# LcsNodes-Extension-Combo-1-Board-B_02_00.net
KiCad netlist of a schematic drawn in EasyEDA
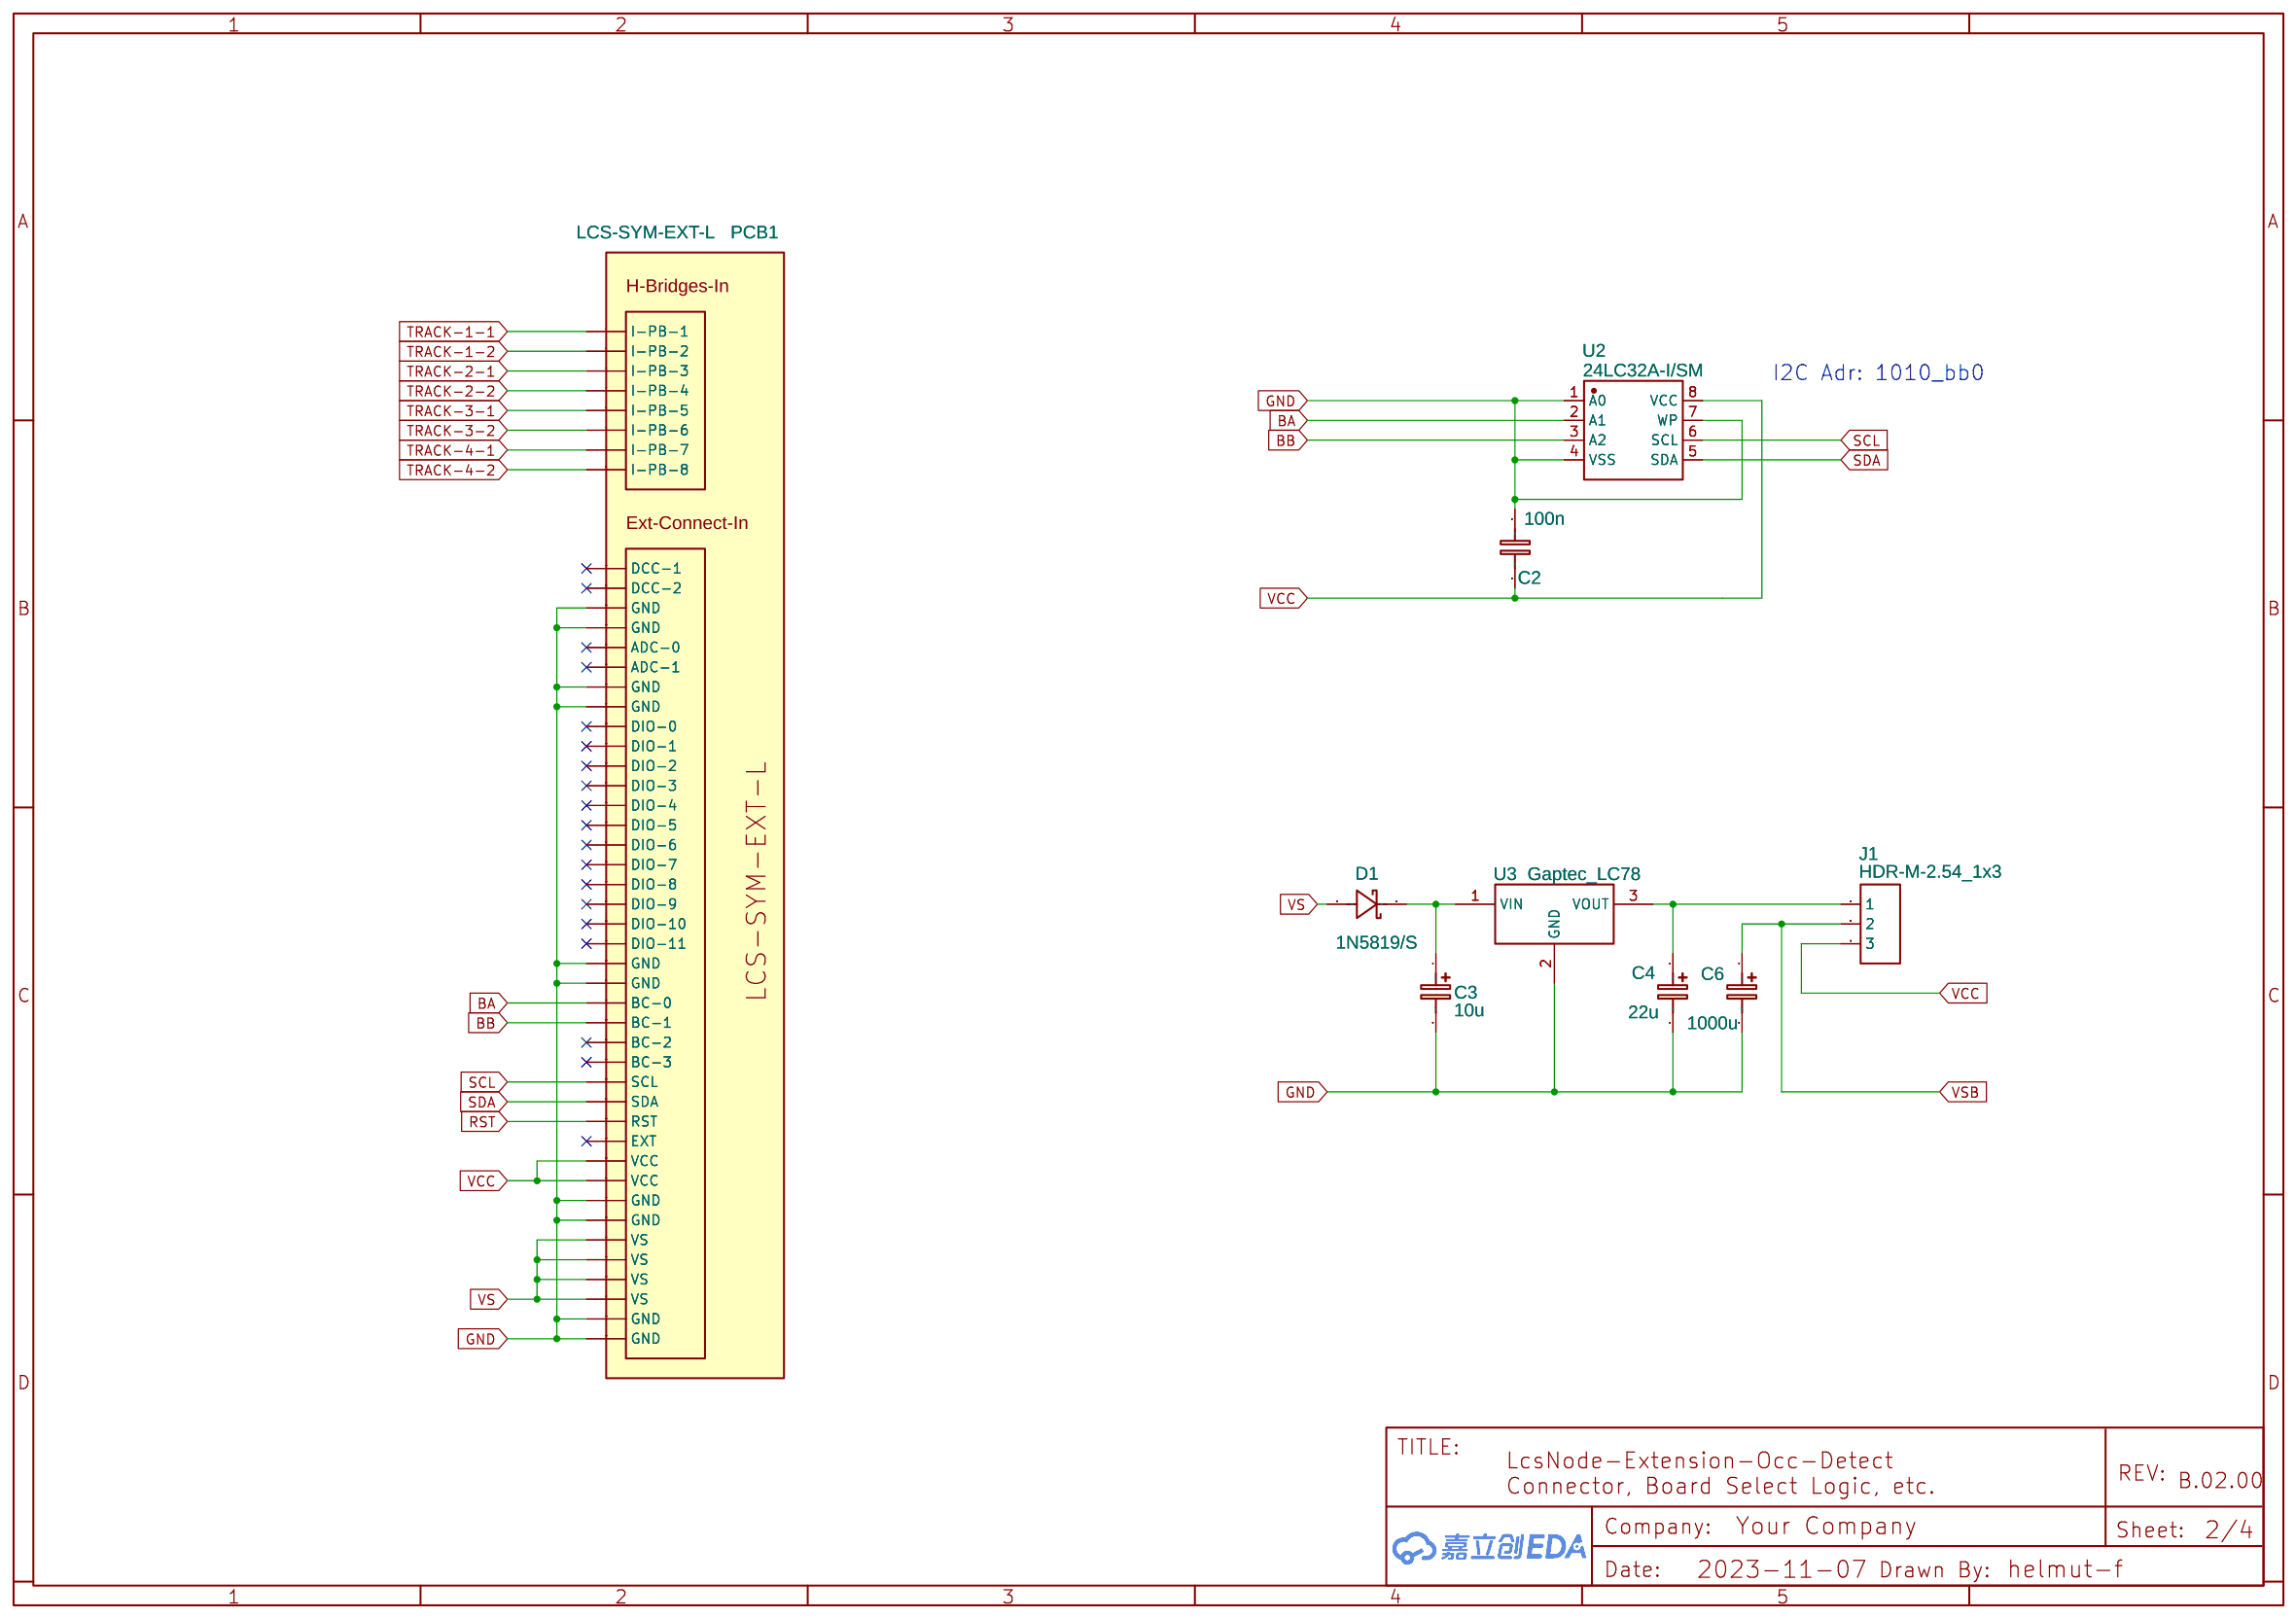
[diagram p0: Connector-and-Logic]
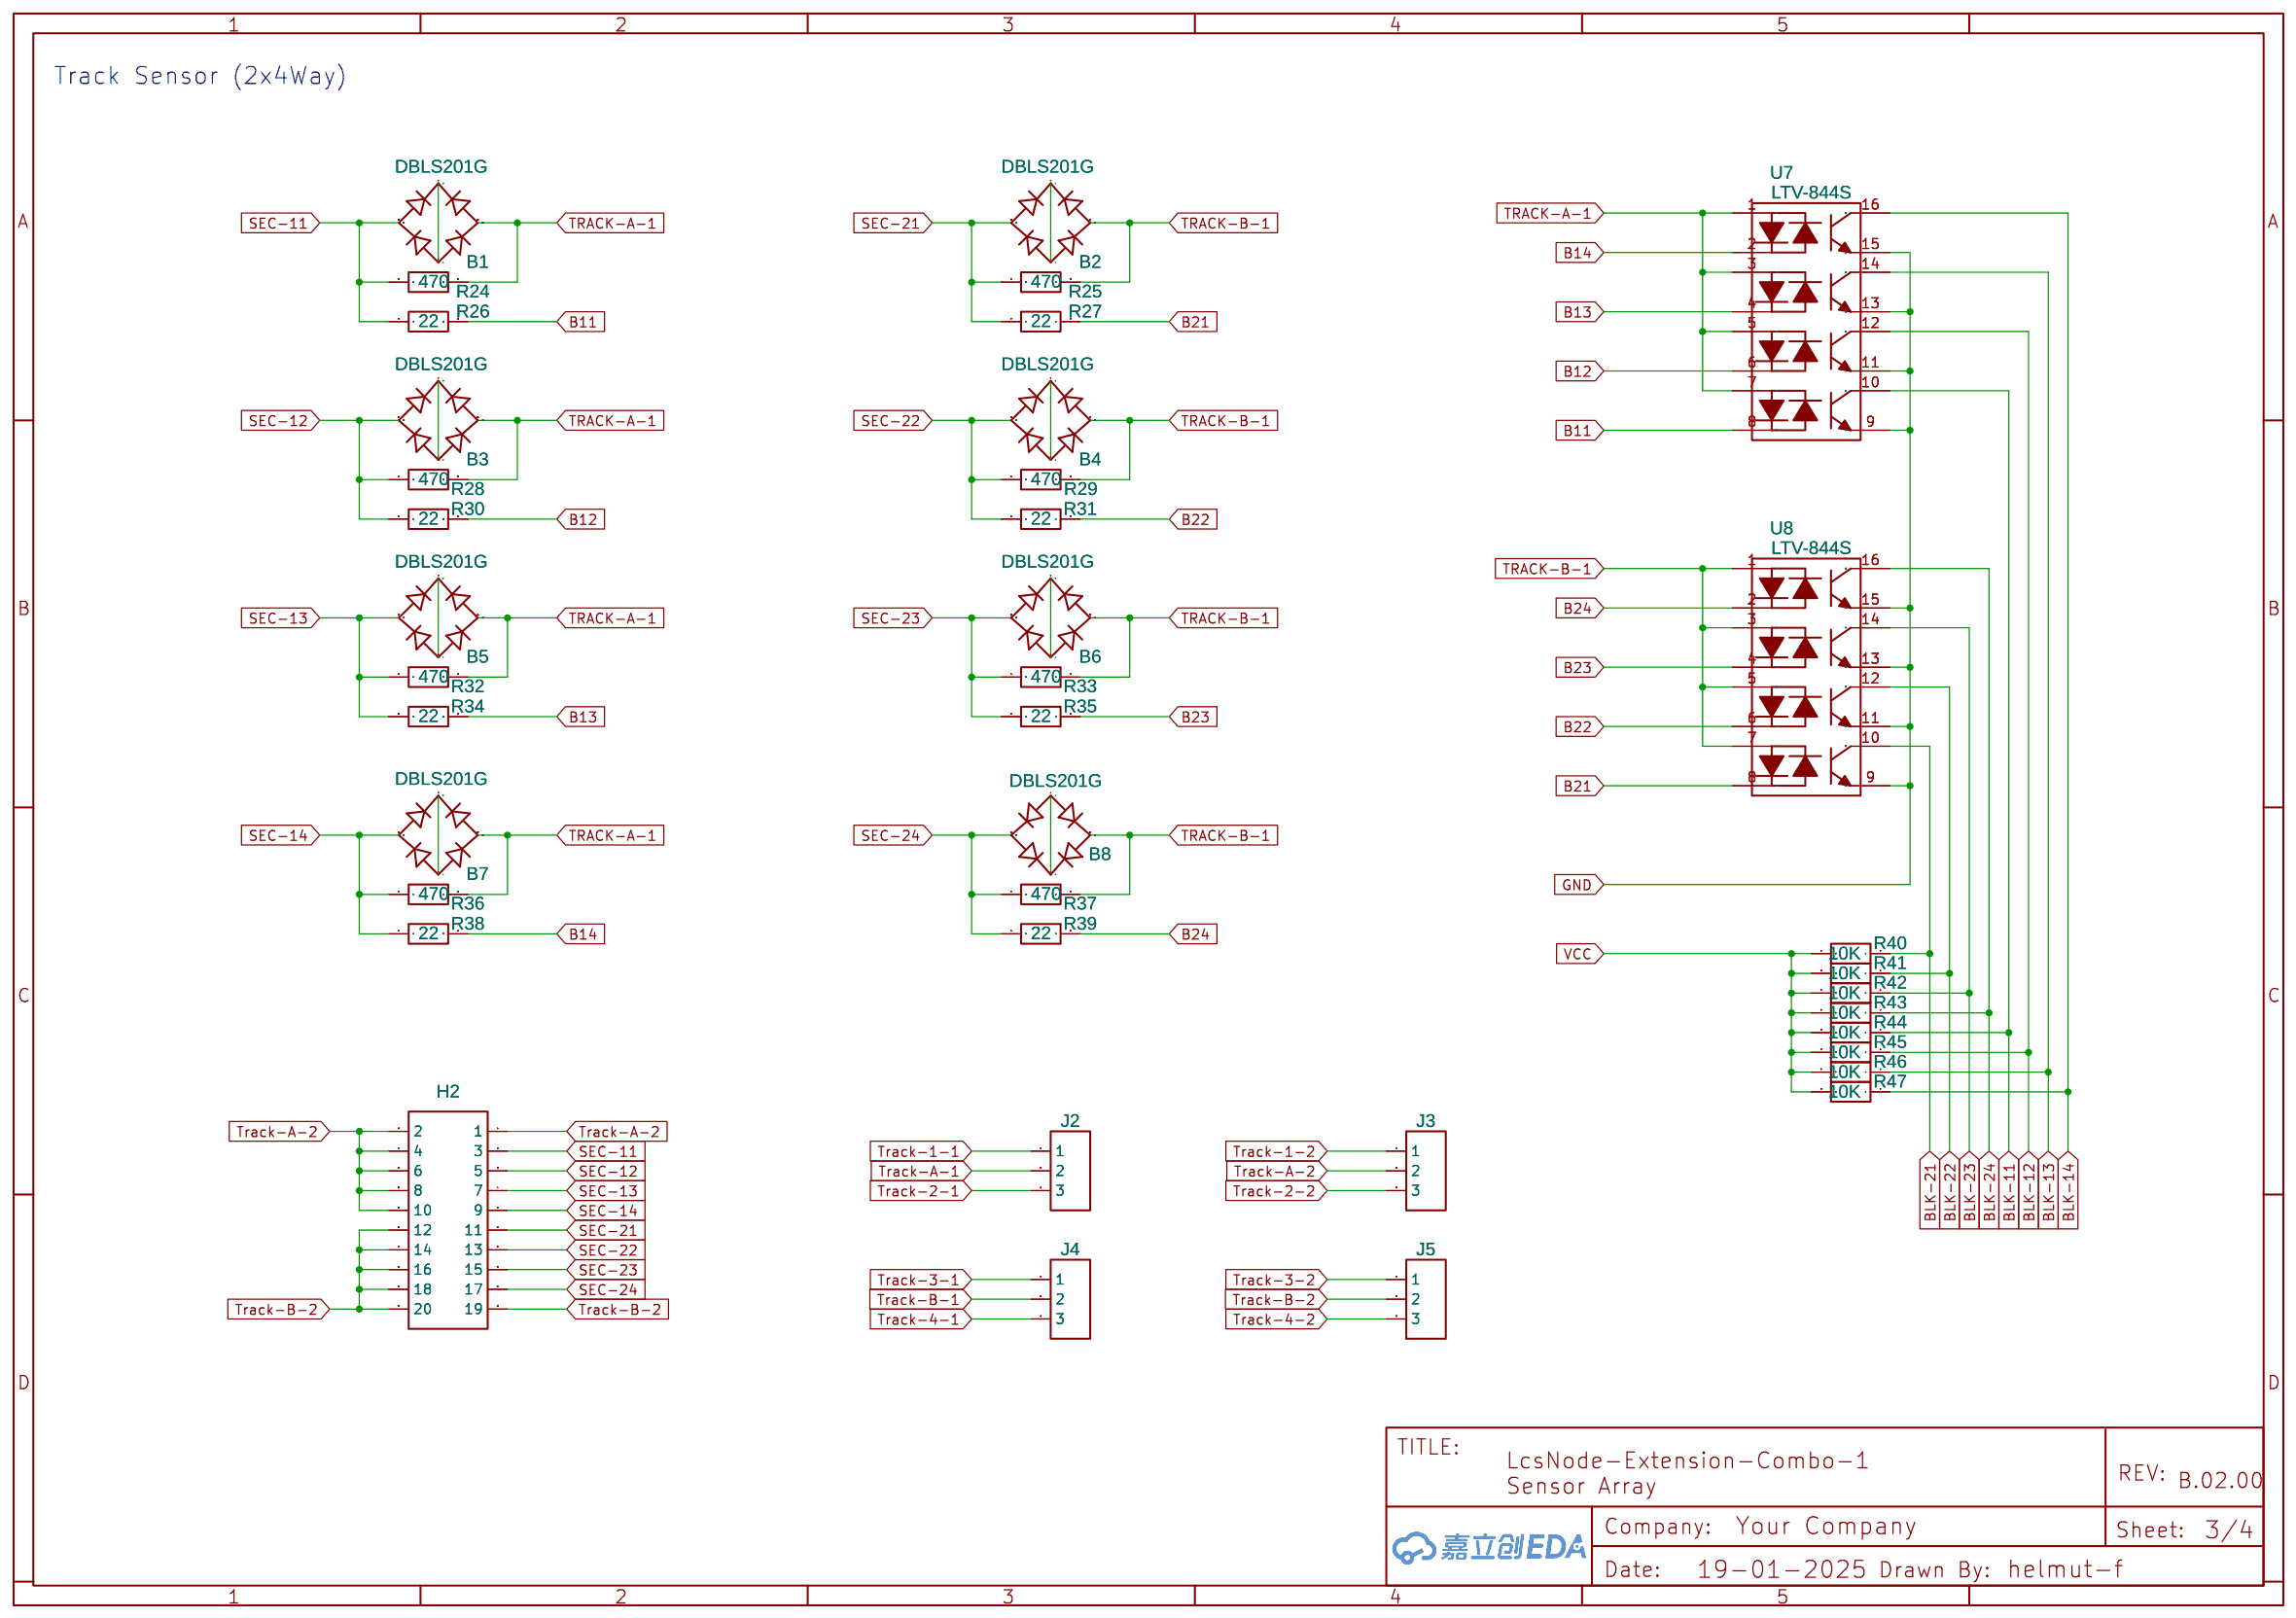
[diagram p1: Sensor-Array]
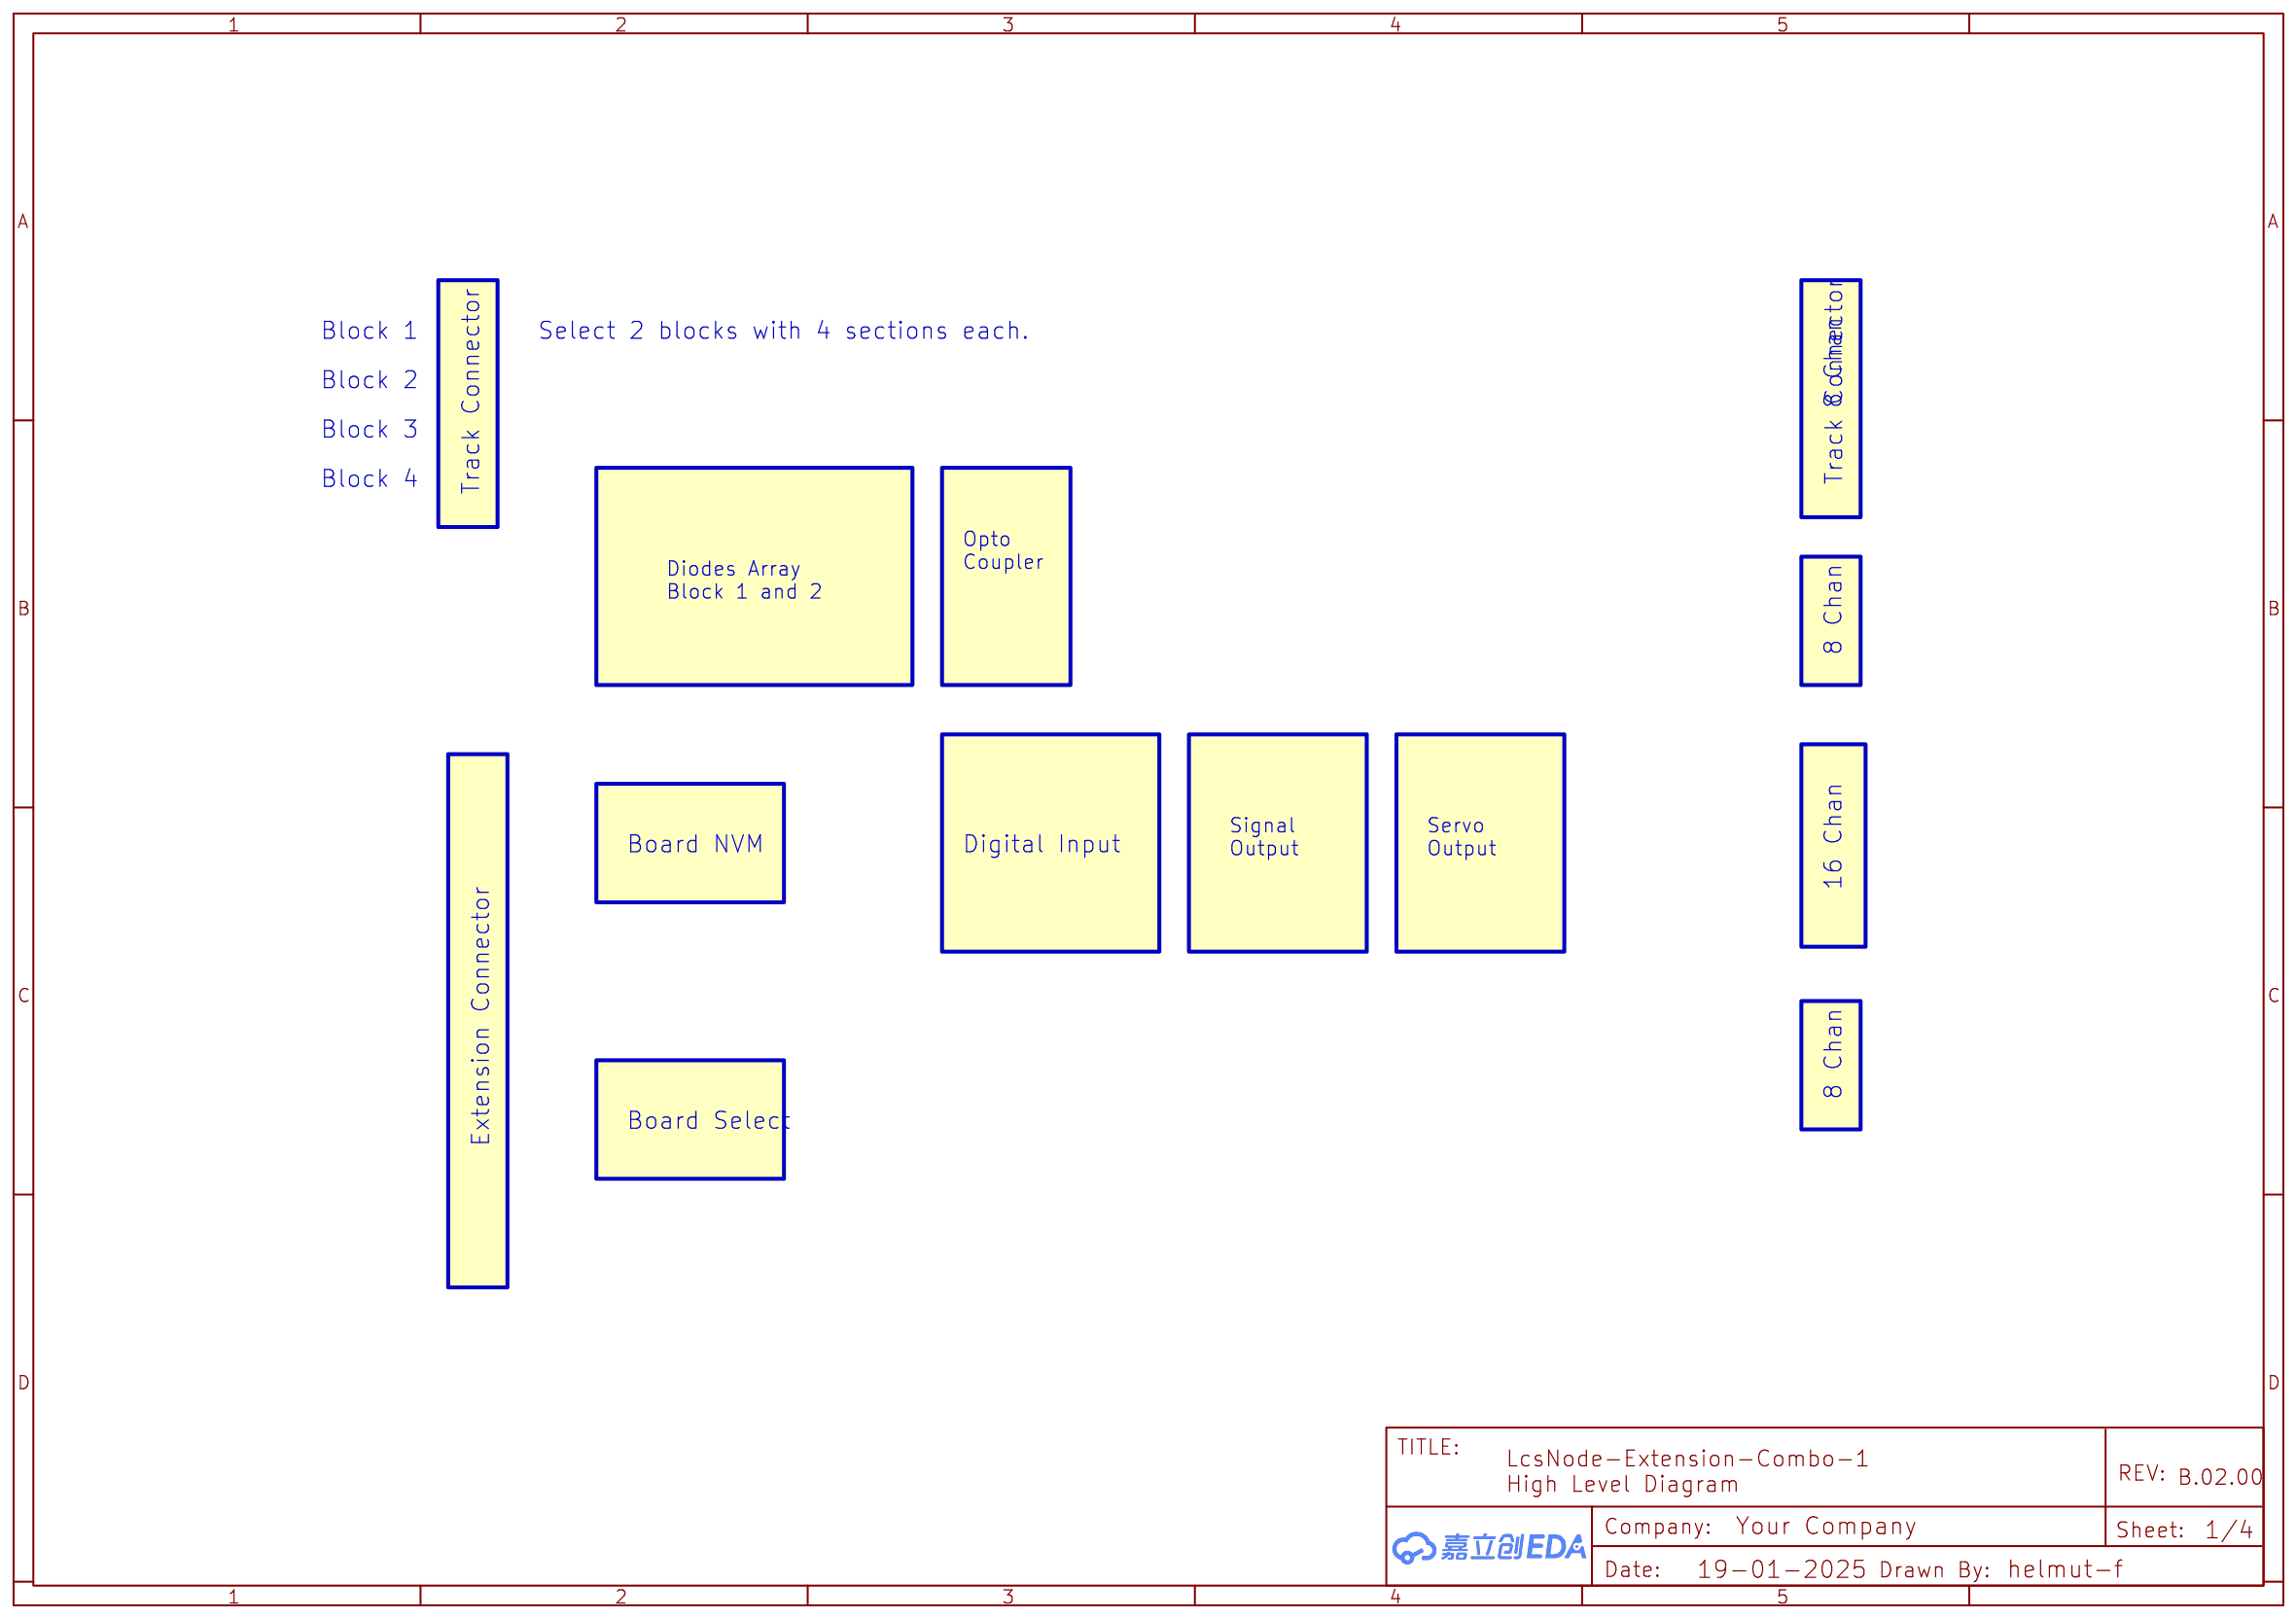
[diagram p2: High Level Schematic]
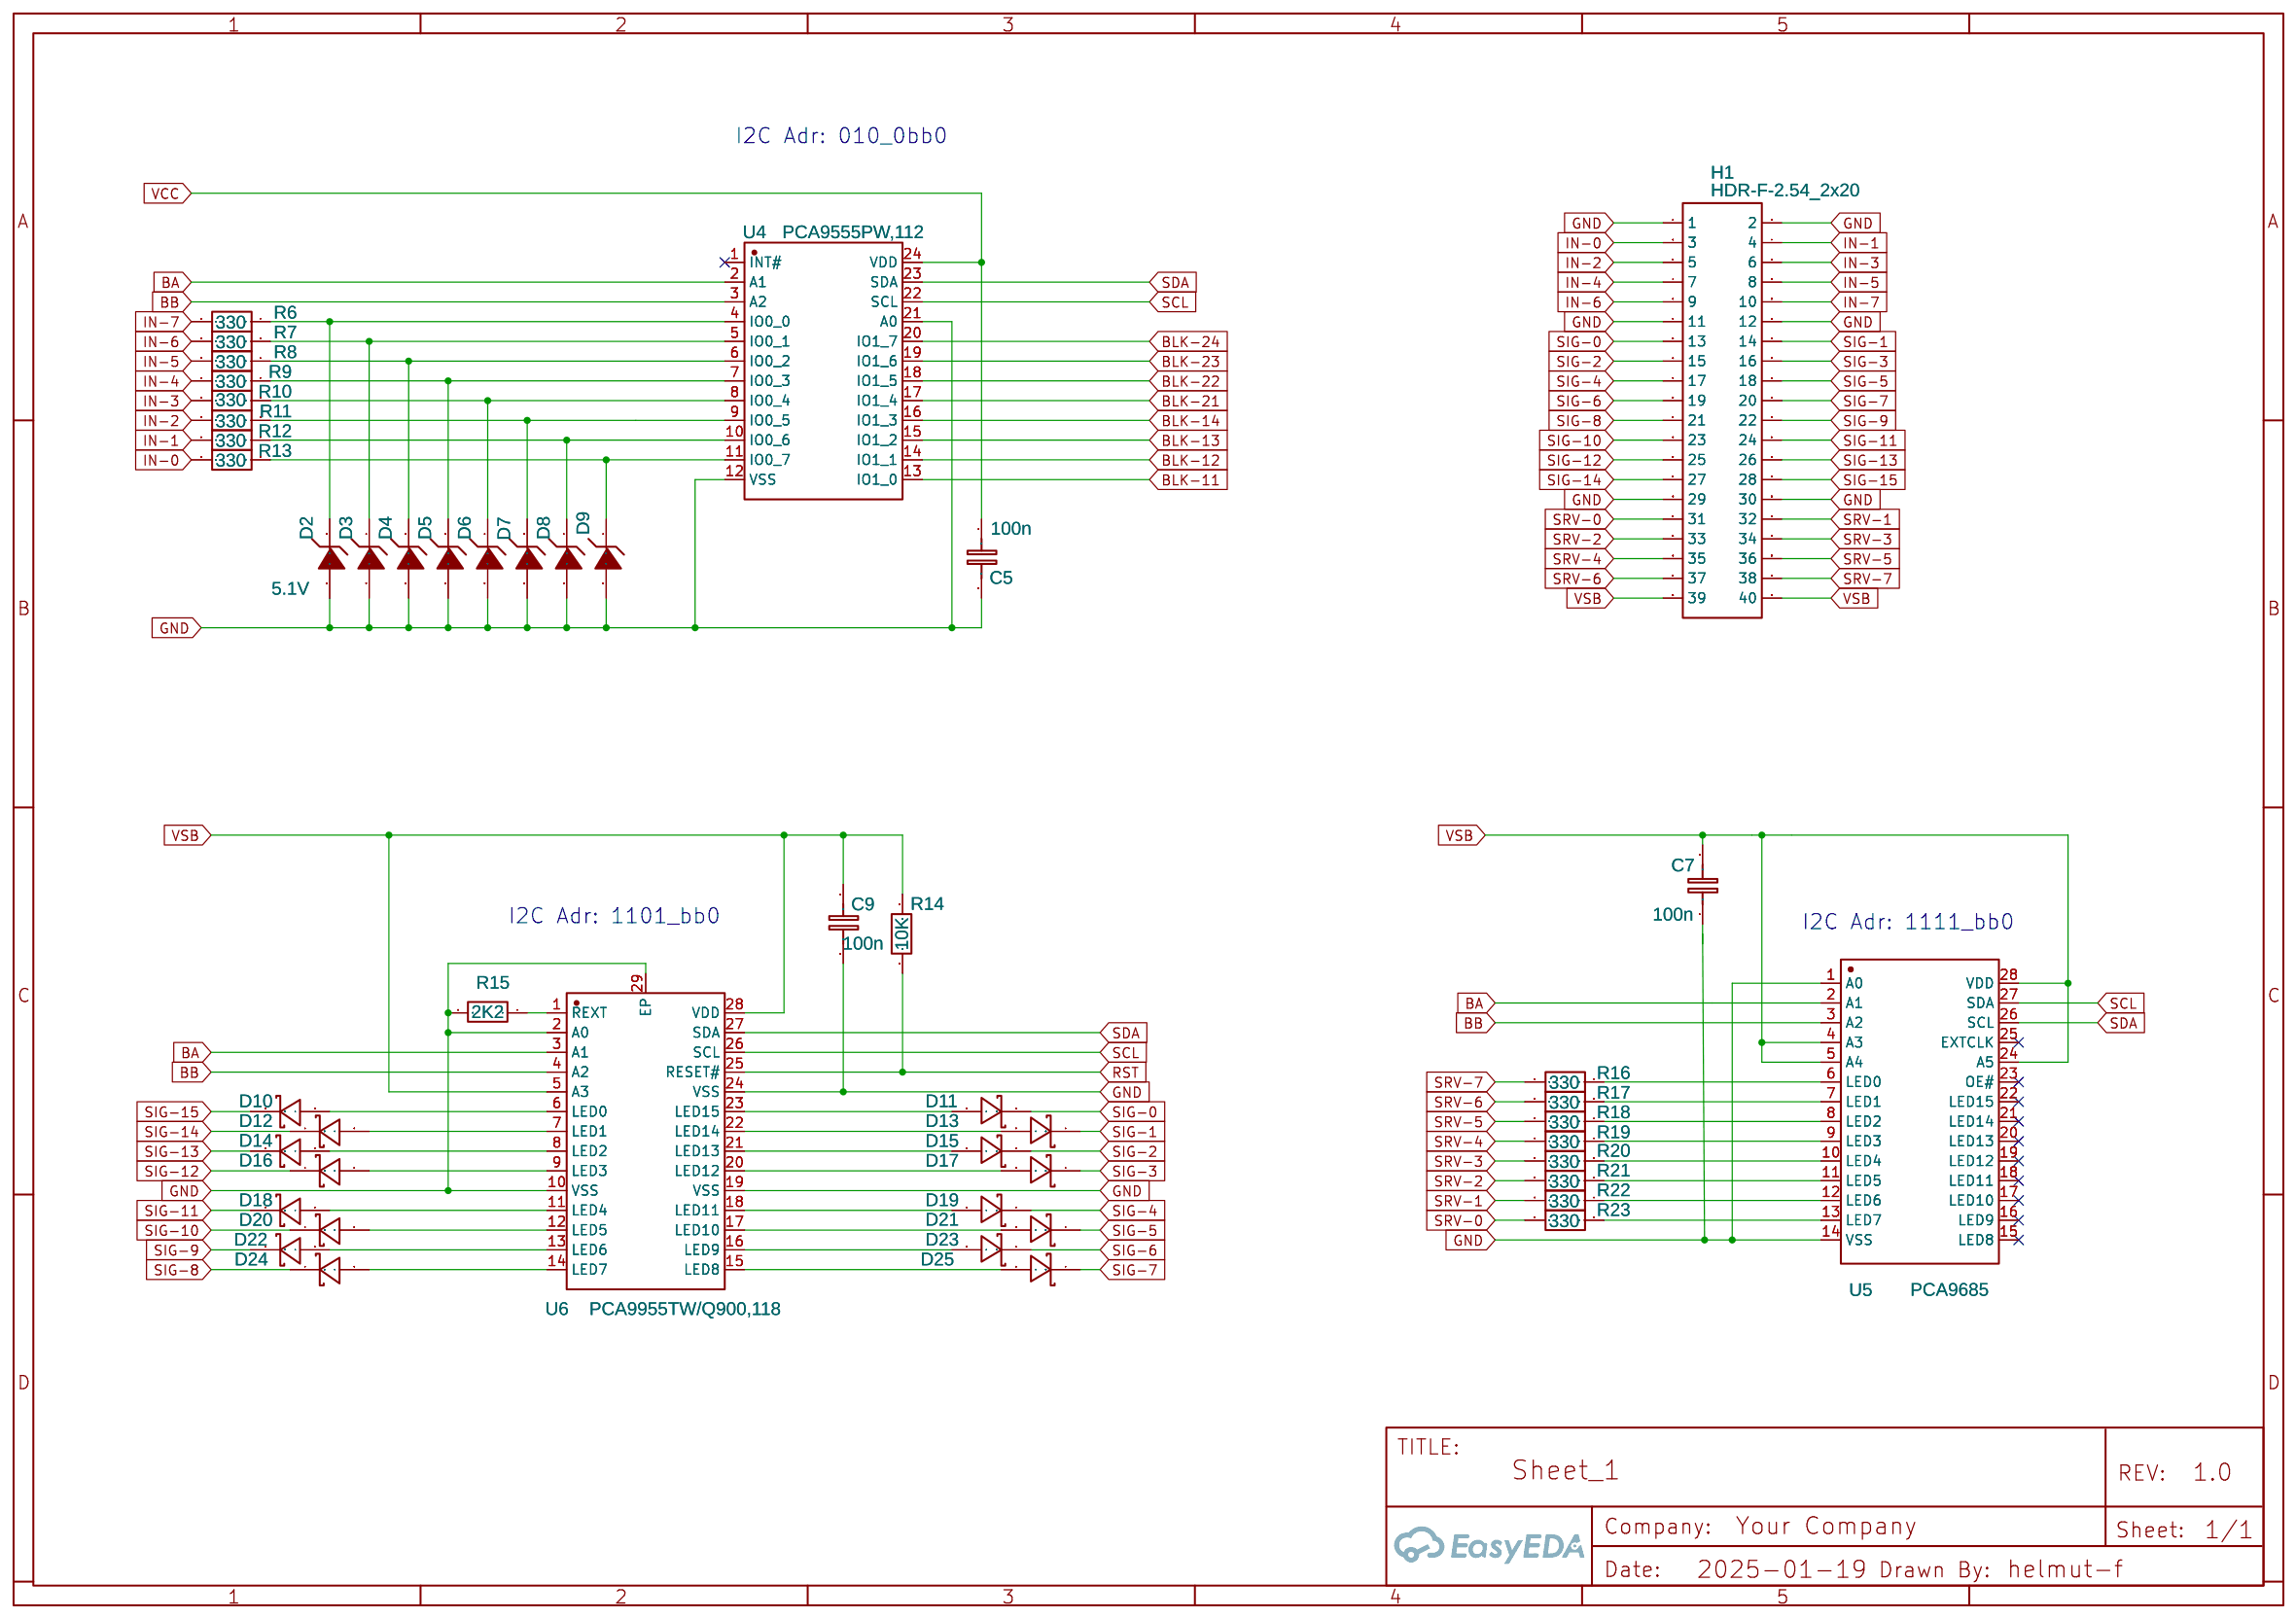
[diagram p3: GPIO, Servo, Signal]

(export (version "E")
  (design (tool "Eeschema 10.0.6"))
  (components
    (comp (ref "C2") (value "100n") (libsource (lib "") (part "C_0603_EU")))
    (comp (ref "C3") (value "10u") (libsource (lib "") (part "CE_SMD_D5.0×H5.5_EU")))
    (comp (ref "C4") (value "22u") (libsource (lib "") (part "CE_SMD_D5.0×H5.5_EU")))
    (comp (ref "C6") (value "1000u") (libsource (lib "") (part "CE_TH_D4.0×F1.5_EU")))
    (comp (ref "D1") (value "1N5819/S") (libsource (lib "") (part "1N5819/S")))
    (comp (ref "J1") (value "HDR-M-2.54_1x3") (libsource (lib "") (part "HDR-M-2.54_1x3")))
    (comp (ref "PCB1") (value "LCS-SYM-EXT-L") (libsource (lib "") (part "LCS-SYM-EXT-L")))
    (comp (ref "U2")
      (value "24LC32A-I/SM")
      (fields (field (name "Manufacturer") "MICROCHIP(美国微芯)"))
      (libsource (lib "") (part "24LC32A-I/SM"))
    )
    (comp (ref "U3") (value "Gaptec_LC78") (libsource (lib "") (part "Gaptec_LC78")))
    (comp (ref "B1") (value "DBLS201G") (libsource (lib "") (part "DBLS201G")))
    (comp (ref "B2") (value "DBLS201G") (libsource (lib "") (part "DBLS201G_2")))
    (comp (ref "B3") (value "DBLS201G") (libsource (lib "") (part "DBLS201G")))
    (comp (ref "B4") (value "DBLS201G") (libsource (lib "") (part "DBLS201G_2")))
    (comp (ref "B5") (value "DBLS201G") (libsource (lib "") (part "DBLS201G")))
    (comp (ref "B6") (value "DBLS201G") (libsource (lib "") (part "DBLS201G_2")))
    (comp (ref "B7") (value "DBLS201G") (libsource (lib "") (part "DBLS201G")))
    (comp (ref "B8") (value "DBLS201G") (libsource (lib "") (part "DBLS201G_1")))
    (comp (ref "H2") (value "HDR-F-2.54_2x10") (libsource (lib "") (part "HDR-F-2.54_2x10")))
    (comp (ref "J2") (value "HDR-M-2.54_1x3") (libsource (lib "") (part "HDR-M-2.54_1x3")))
    (comp (ref "J3") (value "HDR-M-2.54_1x3") (libsource (lib "") (part "HDR-M-2.54_1x3")))
    (comp (ref "J4") (value "HDR-M-2.54_1x3") (libsource (lib "") (part "HDR-M-2.54_1x3")))
    (comp (ref "J5") (value "HDR-M-2.54_1x3") (libsource (lib "") (part "HDR-M-2.54_1x3")))
    (comp (ref "R24") (value "470") (libsource (lib "") (part "R_AXIAL-0.3_EU_1")))
    (comp (ref "R25") (value "470") (libsource (lib "") (part "R_AXIAL-0.3_EU_1")))
    (comp (ref "R26") (value "22") (libsource (lib "") (part "R_AXIAL-0.3_EU_1")))
    (comp (ref "R27") (value "22") (libsource (lib "") (part "R_AXIAL-0.3_EU_1")))
    (comp (ref "R28") (value "470") (libsource (lib "") (part "R_AXIAL-0.3_EU_1")))
    (comp (ref "R29") (value "470") (libsource (lib "") (part "R_AXIAL-0.3_EU_1")))
    (comp (ref "R30") (value "22") (libsource (lib "") (part "R_AXIAL-0.3_EU_1")))
    (comp (ref "R31") (value "22") (libsource (lib "") (part "R_AXIAL-0.3_EU_1")))
    (comp (ref "R32") (value "470") (libsource (lib "") (part "R_AXIAL-0.3_EU_1")))
    (comp (ref "R33") (value "470") (libsource (lib "") (part "R_AXIAL-0.3_EU_1")))
    (comp (ref "R34") (value "22") (libsource (lib "") (part "R_AXIAL-0.3_EU_1")))
    (comp (ref "R35") (value "22") (libsource (lib "") (part "R_AXIAL-0.3_EU_1")))
    (comp (ref "R36") (value "470") (libsource (lib "") (part "R_AXIAL-0.3_EU_1")))
    (comp (ref "R37") (value "470") (libsource (lib "") (part "R_AXIAL-0.3_EU_1")))
    (comp (ref "R38") (value "22") (libsource (lib "") (part "R_AXIAL-0.3_EU_1")))
    (comp (ref "R39") (value "22") (libsource (lib "") (part "R_AXIAL-0.3_EU_1")))
    (comp (ref "R40") (value "10K") (libsource (lib "") (part "R_AXIAL-0.3_EU")))
    (comp (ref "R41") (value "10K") (libsource (lib "") (part "R_AXIAL-0.3_EU")))
    (comp (ref "R42") (value "10K") (libsource (lib "") (part "R_AXIAL-0.3_EU")))
    (comp (ref "R43") (value "10K") (libsource (lib "") (part "R_AXIAL-0.3_EU")))
    (comp (ref "R44") (value "10K") (libsource (lib "") (part "R_AXIAL-0.3_EU")))
    (comp (ref "R45") (value "10K") (libsource (lib "") (part "R_AXIAL-0.3_EU")))
    (comp (ref "R46") (value "10K") (libsource (lib "") (part "R_AXIAL-0.3_EU")))
    (comp (ref "R47") (value "10K") (libsource (lib "") (part "R_AXIAL-0.3_EU")))
    (comp (ref "U7")
      (value "LTV-844S")
      (fields (field (name "Manufacturer") "LITEON(台湾光宝)"))
      (libsource (lib "") (part "LTV-844S"))
    )
    (comp (ref "U8")
      (value "LTV-844S")
      (fields (field (name "Manufacturer") "LITEON(台湾光宝)"))
      (libsource (lib "") (part "LTV-844S"))
    )
    (comp (ref "C5") (value "100n") (libsource (lib "") (part "C_0603_EU")))
    (comp (ref "C7") (value "100n") (libsource (lib "") (part "C_0603_EU_2")))
    (comp (ref "C9") (value "100n") (libsource (lib "") (part "C_0603_EU_1")))
    (comp (ref "D2")
      (value "5.1V")
      (fields (field (name "Manufacturer Part") "Diode Zener") (field (name "Manufacturer") "SEMTECH"))
      (libsource (lib "") (part "Diode Zener"))
    )
    (comp (ref "D3")
      (value "5.1V")
      (fields (field (name "Manufacturer Part") "Diode Zener") (field (name "Manufacturer") "SEMTECH"))
      (libsource (lib "") (part "Diode Zener"))
    )
    (comp (ref "D4")
      (value "5.1V")
      (fields (field (name "Manufacturer Part") "Diode Zener") (field (name "Manufacturer") "SEMTECH"))
      (libsource (lib "") (part "Diode Zener"))
    )
    (comp (ref "D5")
      (value "5.1V")
      (fields (field (name "Manufacturer Part") "Diode Zener") (field (name "Manufacturer") "SEMTECH"))
      (libsource (lib "") (part "Diode Zener"))
    )
    (comp (ref "D6")
      (value "5.1V")
      (fields (field (name "Manufacturer Part") "Diode Zener") (field (name "Manufacturer") "SEMTECH"))
      (libsource (lib "") (part "Diode Zener"))
    )
    (comp (ref "D7")
      (value "5.1V")
      (fields (field (name "Manufacturer Part") "Diode Zener") (field (name "Manufacturer") "SEMTECH"))
      (libsource (lib "") (part "Diode Zener"))
    )
    (comp (ref "D8")
      (value "5.1V")
      (fields (field (name "Manufacturer Part") "Diode Zener") (field (name "Manufacturer") "SEMTECH"))
      (libsource (lib "") (part "Diode Zener"))
    )
    (comp (ref "D9")
      (value "5.1V")
      (fields (field (name "Manufacturer Part") "Diode Zener") (field (name "Manufacturer") "SEMTECH"))
      (libsource (lib "") (part "Diode Zener"))
    )
    (comp (ref "D10")
      (value "BAS85")
      (fields (field (name "Manufacturer") "SHIKUES(时科)"))
      (libsource (lib "") (part "BAS85"))
    )
    (comp (ref "D11")
      (value "BAS85")
      (fields (field (name "Manufacturer") "SHIKUES(时科)"))
      (libsource (lib "") (part "BAS85_1"))
    )
    (comp (ref "D12")
      (value "BAS85")
      (fields (field (name "Manufacturer") "SHIKUES(时科)"))
      (libsource (lib "") (part "BAS85"))
    )
    (comp (ref "D13")
      (value "BAS85")
      (fields (field (name "Manufacturer") "SHIKUES(时科)"))
      (libsource (lib "") (part "BAS85_1"))
    )
    (comp (ref "D14")
      (value "BAS85")
      (fields (field (name "Manufacturer") "SHIKUES(时科)"))
      (libsource (lib "") (part "BAS85"))
    )
    (comp (ref "D15")
      (value "BAS85")
      (fields (field (name "Manufacturer") "SHIKUES(时科)"))
      (libsource (lib "") (part "BAS85_1"))
    )
    (comp (ref "D16")
      (value "BAS85")
      (fields (field (name "Manufacturer") "SHIKUES(时科)"))
      (libsource (lib "") (part "BAS85"))
    )
    (comp (ref "D17")
      (value "BAS85")
      (fields (field (name "Manufacturer") "SHIKUES(时科)"))
      (libsource (lib "") (part "BAS85_1"))
    )
    (comp (ref "D18")
      (value "BAS85")
      (fields (field (name "Manufacturer") "SHIKUES(时科)"))
      (libsource (lib "") (part "BAS85"))
    )
    (comp (ref "D19")
      (value "BAS85")
      (fields (field (name "Manufacturer") "SHIKUES(时科)"))
      (libsource (lib "") (part "BAS85_1"))
    )
    (comp (ref "D20")
      (value "BAS85")
      (fields (field (name "Manufacturer") "SHIKUES(时科)"))
      (libsource (lib "") (part "BAS85"))
    )
    (comp (ref "D21")
      (value "BAS85")
      (fields (field (name "Manufacturer") "SHIKUES(时科)"))
      (libsource (lib "") (part "BAS85_1"))
    )
    (comp (ref "D22")
      (value "BAS85")
      (fields (field (name "Manufacturer") "SHIKUES(时科)"))
      (libsource (lib "") (part "BAS85"))
    )
    (comp (ref "D23")
      (value "BAS85")
      (fields (field (name "Manufacturer") "SHIKUES(时科)"))
      (libsource (lib "") (part "BAS85_1"))
    )
    (comp (ref "D24")
      (value "BAS85")
      (fields (field (name "Manufacturer") "SHIKUES(时科)"))
      (libsource (lib "") (part "BAS85"))
    )
    (comp (ref "D25")
      (value "BAS85")
      (fields (field (name "Manufacturer") "SHIKUES(时科)"))
      (libsource (lib "") (part "BAS85_1"))
    )
    (comp (ref "H1") (value "HDR-F-2.54_2x20") (libsource (lib "") (part "HDR-F-2.54_2x20")))
    (comp (ref "R6") (value "330") (libsource (lib "") (part "R_AXIAL-0.3_EU")))
    (comp (ref "R7") (value "330") (libsource (lib "") (part "R_AXIAL-0.3_EU")))
    (comp (ref "R8") (value "330") (libsource (lib "") (part "R_AXIAL-0.3_EU")))
    (comp (ref "R9") (value "330") (libsource (lib "") (part "R_AXIAL-0.3_EU")))
    (comp (ref "R10") (value "330") (libsource (lib "") (part "R_AXIAL-0.3_EU")))
    (comp (ref "R11") (value "330") (libsource (lib "") (part "R_AXIAL-0.3_EU")))
    (comp (ref "R12") (value "330") (libsource (lib "") (part "R_AXIAL-0.3_EU")))
    (comp (ref "R13") (value "330") (libsource (lib "") (part "R_AXIAL-0.3_EU")))
    (comp (ref "R14") (value "10K") (libsource (lib "") (part "R_AXIAL-0.3_EU_1")))
    (comp (ref "R15") (value "2K2") (libsource (lib "") (part "R_AXIAL-0.3_EU_2")))
    (comp (ref "R16") (value "330") (libsource (lib "") (part "R_AXIAL-0.3_EU")))
    (comp (ref "R17") (value "330") (libsource (lib "") (part "R_AXIAL-0.3_EU")))
    (comp (ref "R18") (value "330") (libsource (lib "") (part "R_AXIAL-0.3_EU")))
    (comp (ref "R19") (value "330") (libsource (lib "") (part "R_AXIAL-0.3_EU")))
    (comp (ref "R20") (value "330") (libsource (lib "") (part "R_AXIAL-0.3_EU")))
    (comp (ref "R21") (value "330") (libsource (lib "") (part "R_AXIAL-0.3_EU")))
    (comp (ref "R22") (value "330") (libsource (lib "") (part "R_AXIAL-0.3_EU")))
    (comp (ref "R23") (value "330") (libsource (lib "") (part "R_AXIAL-0.3_EU")))
    (comp (ref "U4")
      (value "PCA9555PW,112")
      (fields (field (name "Manufacturer") "NXP(恩智浦)"))
      (libsource (lib "") (part "PCA9555PW,112"))
    )
    (comp (ref "U5")
      (value "PCA9685")
      (fields (field (name "Manufacturer Part") "PCA9685PW/Q900,118") (field (name "Manufacturer") "NXP"))
      (libsource (lib "") (part "PCA9685PW/Q900,118"))
    )
    (comp (ref "U6")
      (value "PCA9955TW/Q900,118")
      (fields (field (name "Manufacturer") "NXP(恩智浦)"))
      (libsource (lib "") (part "PCA9955TW/Q900,118"))
    )
  )
  (nets
    (net (code "1") (name "B11") (class "Default")
      (node (ref "R26") (pin "2") (pinfunction "2_2") (pintype "unspecified"))
      (node (ref "U7") (pin "8") (pinfunction "8_8") (pintype "unspecified"))
    )
    (net (code "2") (name "B12") (class "Default")
      (node (ref "R30") (pin "2") (pinfunction "2_2") (pintype "unspecified"))
      (node (ref "U7") (pin "6") (pinfunction "6_6") (pintype "unspecified"))
    )
    (net (code "3") (name "B13") (class "Default")
      (node (ref "R34") (pin "2") (pinfunction "2_2") (pintype "unspecified"))
      (node (ref "U7") (pin "4") (pinfunction "4_4") (pintype "unspecified"))
    )
    (net (code "4") (name "B14") (class "Default")
      (node (ref "R38") (pin "2") (pinfunction "2_2") (pintype "unspecified"))
      (node (ref "U7") (pin "2") (pinfunction "2_2") (pintype "unspecified"))
    )
    (net (code "5") (name "B21") (class "Default")
      (node (ref "R27") (pin "2") (pinfunction "2_2") (pintype "unspecified"))
      (node (ref "U8") (pin "8") (pinfunction "8_8") (pintype "unspecified"))
    )
    (net (code "6") (name "B22") (class "Default")
      (node (ref "R31") (pin "2") (pinfunction "2_2") (pintype "unspecified"))
      (node (ref "U8") (pin "6") (pinfunction "6_6") (pintype "unspecified"))
    )
    (net (code "7") (name "B23") (class "Default")
      (node (ref "R35") (pin "2") (pinfunction "2_2") (pintype "unspecified"))
      (node (ref "U8") (pin "4") (pinfunction "4_4") (pintype "unspecified"))
    )
    (net (code "8") (name "B24") (class "Default")
      (node (ref "R39") (pin "2") (pinfunction "2_2") (pintype "unspecified"))
      (node (ref "U8") (pin "2") (pinfunction "2_2") (pintype "unspecified"))
    )
    (net (code "9") (name "BA") (class "Default")
      (node (ref "PCB1") (pin "32") (pinfunction "BC-0_32") (pintype "unspecified"))
      (node (ref "U2") (pin "2") (pinfunction "A1_2") (pintype "unspecified"))
      (node (ref "U4") (pin "2") (pinfunction "A1_2") (pintype "unspecified"))
      (node (ref "U5") (pin "2") (pinfunction "A1_2") (pintype "unspecified"))
      (node (ref "U6") (pin "3") (pinfunction "A1_3") (pintype "unspecified"))
    )
    (net (code "10") (name "BB") (class "Default")
      (node (ref "PCB1") (pin "33") (pinfunction "BC-1_33") (pintype "unspecified"))
      (node (ref "U2") (pin "3") (pinfunction "A2_3") (pintype "unspecified"))
      (node (ref "U4") (pin "3") (pinfunction "A2_3") (pintype "unspecified"))
      (node (ref "U5") (pin "3") (pinfunction "A2_3") (pintype "unspecified"))
      (node (ref "U6") (pin "4") (pinfunction "A2_4") (pintype "unspecified"))
    )
    (net (code "11") (name "BLK-11") (class "Default")
      (node (ref "R44") (pin "1") (pinfunction "1_1") (pintype "unspecified"))
      (node (ref "U4") (pin "13") (pinfunction "IO1_0_13") (pintype "unspecified"))
      (node (ref "U7") (pin "10") (pinfunction "10_10") (pintype "unspecified"))
    )
    (net (code "12") (name "BLK-12") (class "Default")
      (node (ref "R45") (pin "1") (pinfunction "1_1") (pintype "unspecified"))
      (node (ref "U4") (pin "14") (pinfunction "IO1_1_14") (pintype "unspecified"))
      (node (ref "U7") (pin "12") (pinfunction "12_12") (pintype "unspecified"))
    )
    (net (code "13") (name "BLK-13") (class "Default")
      (node (ref "R46") (pin "1") (pinfunction "1_1") (pintype "unspecified"))
      (node (ref "U4") (pin "15") (pinfunction "IO1_2_15") (pintype "unspecified"))
      (node (ref "U7") (pin "14") (pinfunction "14_14") (pintype "unspecified"))
    )
    (net (code "14") (name "BLK-14") (class "Default")
      (node (ref "R47") (pin "1") (pinfunction "1_1") (pintype "unspecified"))
      (node (ref "U4") (pin "16") (pinfunction "IO1_3_16") (pintype "unspecified"))
      (node (ref "U7") (pin "16") (pinfunction "16_16") (pintype "unspecified"))
    )
    (net (code "15") (name "BLK-21") (class "Default")
      (node (ref "R40") (pin "1") (pinfunction "1_1") (pintype "unspecified"))
      (node (ref "U4") (pin "17") (pinfunction "IO1_4_17") (pintype "unspecified"))
      (node (ref "U8") (pin "10") (pinfunction "10_10") (pintype "unspecified"))
    )
    (net (code "16") (name "BLK-22") (class "Default")
      (node (ref "R41") (pin "1") (pinfunction "1_1") (pintype "unspecified"))
      (node (ref "U4") (pin "18") (pinfunction "IO1_5_18") (pintype "unspecified"))
      (node (ref "U8") (pin "12") (pinfunction "12_12") (pintype "unspecified"))
    )
    (net (code "17") (name "BLK-23") (class "Default")
      (node (ref "R42") (pin "1") (pinfunction "1_1") (pintype "unspecified"))
      (node (ref "U4") (pin "19") (pinfunction "IO1_6_19") (pintype "unspecified"))
      (node (ref "U8") (pin "14") (pinfunction "14_14") (pintype "unspecified"))
    )
    (net (code "18") (name "BLK-24") (class "Default")
      (node (ref "R43") (pin "1") (pinfunction "1_1") (pintype "unspecified"))
      (node (ref "U4") (pin "20") (pinfunction "IO1_7_20") (pintype "unspecified"))
      (node (ref "U8") (pin "16") (pinfunction "16_16") (pintype "unspecified"))
    )
    (net (code "19") (name "GND") (class "Default")
      (node (ref "C2") (pin "1") (pinfunction "1_1") (pintype "unspecified"))
      (node (ref "C3") (pin "2") (pinfunction "2_2") (pintype "unspecified"))
      (node (ref "C4") (pin "2") (pinfunction "2_2") (pintype "unspecified"))
      (node (ref "C5") (pin "2") (pinfunction "2_2") (pintype "unspecified"))
      (node (ref "C6") (pin "2") (pinfunction "2_2") (pintype "unspecified"))
      (node (ref "C7") (pin "1") (pinfunction "1_1") (pintype "unspecified"))
      (node (ref "C9") (pin "2") (pinfunction "2_2") (pintype "unspecified"))
      (node (ref "D2") (pin "2") (pinfunction "A_2") (pintype "unspecified"))
      (node (ref "D3") (pin "2") (pinfunction "A_2") (pintype "unspecified"))
      (node (ref "D4") (pin "2") (pinfunction "A_2") (pintype "unspecified"))
      (node (ref "D5") (pin "2") (pinfunction "A_2") (pintype "unspecified"))
      (node (ref "D6") (pin "2") (pinfunction "A_2") (pintype "unspecified"))
      (node (ref "D7") (pin "2") (pinfunction "A_2") (pintype "unspecified"))
      (node (ref "D8") (pin "2") (pinfunction "A_2") (pintype "unspecified"))
      (node (ref "D9") (pin "2") (pinfunction "A_2") (pintype "unspecified"))
      (node (ref "H1") (pin "1") (pinfunction "1_1") (pintype "input"))
      (node (ref "H1") (pin "11") (pinfunction "11_11") (pintype "input"))
      (node (ref "H1") (pin "12") (pinfunction "12_12") (pintype "input"))
      (node (ref "H1") (pin "2") (pinfunction "2_2") (pintype "input"))
      (node (ref "H1") (pin "29") (pinfunction "29_29") (pintype "input"))
      (node (ref "H1") (pin "30") (pinfunction "30_30") (pintype "input"))
      (node (ref "PCB1") (pin "12") (pinfunction "GND_12") (pintype "unspecified"))
      (node (ref "PCB1") (pin "13") (pinfunction "GND_13") (pintype "unspecified"))
      (node (ref "PCB1") (pin "16") (pinfunction "GND_16") (pintype "unspecified"))
      (node (ref "PCB1") (pin "17") (pinfunction "GND_17") (pintype "unspecified"))
      (node (ref "PCB1") (pin "30") (pinfunction "GND_30") (pintype "unspecified"))
      (node (ref "PCB1") (pin "31") (pinfunction "GND_31") (pintype "unspecified"))
      (node (ref "PCB1") (pin "42") (pinfunction "GND_42") (pintype "unspecified"))
      (node (ref "PCB1") (pin "43") (pinfunction "GND_43") (pintype "unspecified"))
      (node (ref "PCB1") (pin "48") (pinfunction "GND_48") (pintype "unspecified"))
      (node (ref "PCB1") (pin "49") (pinfunction "GND_49") (pintype "unspecified"))
      (node (ref "R15") (pin "2") (pinfunction "2_2") (pintype "unspecified"))
      (node (ref "U2") (pin "1") (pinfunction "A0_1") (pintype "unspecified"))
      (node (ref "U2") (pin "4") (pinfunction "VSS_4") (pintype "unspecified"))
      (node (ref "U2") (pin "7") (pinfunction "WP_7") (pintype "unspecified"))
      (node (ref "U3") (pin "2") (pinfunction "GND_2") (pintype "unspecified"))
      (node (ref "U4") (pin "12") (pinfunction "VSS_12") (pintype "unspecified"))
      (node (ref "U4") (pin "21") (pinfunction "A0_21") (pintype "unspecified"))
      (node (ref "U5") (pin "1") (pinfunction "A0_1") (pintype "unspecified"))
      (node (ref "U5") (pin "14") (pinfunction "VSS_14") (pintype "unspecified"))
      (node (ref "U6") (pin "10") (pinfunction "VSS_10") (pintype "unspecified"))
      (node (ref "U6") (pin "19") (pinfunction "VSS_19") (pintype "unspecified"))
      (node (ref "U6") (pin "2") (pinfunction "A0_2") (pintype "unspecified"))
      (node (ref "U6") (pin "24") (pinfunction "VSS_24") (pintype "unspecified"))
      (node (ref "U6") (pin "29") (pinfunction "EP_29") (pintype "unspecified"))
      (node (ref "U7") (pin "11") (pinfunction "11_11") (pintype "unspecified"))
      (node (ref "U7") (pin "13") (pinfunction "13_13") (pintype "unspecified"))
      (node (ref "U7") (pin "15") (pinfunction "15_15") (pintype "unspecified"))
      (node (ref "U7") (pin "9") (pinfunction "9_9") (pintype "unspecified"))
      (node (ref "U8") (pin "11") (pinfunction "11_11") (pintype "unspecified"))
      (node (ref "U8") (pin "13") (pinfunction "13_13") (pintype "unspecified"))
      (node (ref "U8") (pin "15") (pinfunction "15_15") (pintype "unspecified"))
      (node (ref "U8") (pin "9") (pinfunction "9_9") (pintype "unspecified"))
    )
    (net (code "20") (name "IN-0") (class "Default")
      (node (ref "H1") (pin "3") (pinfunction "3_3") (pintype "input"))
      (node (ref "R13") (pin "2") (pinfunction "2_2") (pintype "unspecified"))
    )
    (net (code "21") (name "IN-1") (class "Default")
      (node (ref "H1") (pin "4") (pinfunction "4_4") (pintype "input"))
      (node (ref "R12") (pin "2") (pinfunction "2_2") (pintype "unspecified"))
    )
    (net (code "22") (name "IN-2") (class "Default")
      (node (ref "H1") (pin "5") (pinfunction "5_5") (pintype "input"))
      (node (ref "R11") (pin "2") (pinfunction "2_2") (pintype "unspecified"))
    )
    (net (code "23") (name "IN-3") (class "Default")
      (node (ref "H1") (pin "6") (pinfunction "6_6") (pintype "input"))
      (node (ref "R10") (pin "2") (pinfunction "2_2") (pintype "unspecified"))
    )
    (net (code "24") (name "IN-4") (class "Default")
      (node (ref "H1") (pin "7") (pinfunction "7_7") (pintype "input"))
      (node (ref "R9") (pin "2") (pinfunction "2_2") (pintype "unspecified"))
    )
    (net (code "25") (name "IN-5") (class "Default")
      (node (ref "H1") (pin "8") (pinfunction "8_8") (pintype "input"))
      (node (ref "R8") (pin "2") (pinfunction "2_2") (pintype "unspecified"))
    )
    (net (code "26") (name "IN-6") (class "Default")
      (node (ref "H1") (pin "9") (pinfunction "9_9") (pintype "input"))
      (node (ref "R7") (pin "2") (pinfunction "2_2") (pintype "unspecified"))
    )
    (net (code "27") (name "IN-7") (class "Default")
      (node (ref "H1") (pin "10") (pinfunction "10_10") (pintype "input"))
      (node (ref "R6") (pin "2") (pinfunction "2_2") (pintype "unspecified"))
    )
    (net (code "28") (name "Net-(B1-Pad+)") (class "Default")
      (node (ref "B1") (pin "+") (pinfunction "+_+") (pintype "unspecified"))
      (node (ref "B1") (pin "-") (pinfunction "-_-") (pintype "unspecified"))
    )
    (net (code "29") (name "Net-(B2-Pad+)") (class "Default")
      (node (ref "B2") (pin "+") (pinfunction "+_+") (pintype "unspecified"))
      (node (ref "B2") (pin "-") (pinfunction "-_-") (pintype "unspecified"))
    )
    (net (code "30") (name "Net-(B3-Pad+)") (class "Default")
      (node (ref "B3") (pin "+") (pinfunction "+_+") (pintype "unspecified"))
      (node (ref "B3") (pin "-") (pinfunction "-_-") (pintype "unspecified"))
    )
    (net (code "31") (name "Net-(B4-Pad+)") (class "Default")
      (node (ref "B4") (pin "+") (pinfunction "+_+") (pintype "unspecified"))
      (node (ref "B4") (pin "-") (pinfunction "-_-") (pintype "unspecified"))
    )
    (net (code "32") (name "Net-(B5-Pad+)") (class "Default")
      (node (ref "B5") (pin "+") (pinfunction "+_+") (pintype "unspecified"))
      (node (ref "B5") (pin "-") (pinfunction "-_-") (pintype "unspecified"))
    )
    (net (code "33") (name "Net-(B6-Pad+)") (class "Default")
      (node (ref "B6") (pin "+") (pinfunction "+_+") (pintype "unspecified"))
      (node (ref "B6") (pin "-") (pinfunction "-_-") (pintype "unspecified"))
    )
    (net (code "34") (name "Net-(B7-Pad+)") (class "Default")
      (node (ref "B7") (pin "+") (pinfunction "+_+") (pintype "unspecified"))
      (node (ref "B7") (pin "-") (pinfunction "-_-") (pintype "unspecified"))
    )
    (net (code "35") (name "Net-(B8-Pad+)") (class "Default")
      (node (ref "B8") (pin "+") (pinfunction "+_+") (pintype "unspecified"))
      (node (ref "B8") (pin "-") (pinfunction "-_-") (pintype "unspecified"))
    )
    (net (code "36") (name "Net-(D1-K)") (class "Default")
      (node (ref "C3") (pin "1") (pinfunction "1_1") (pintype "unspecified"))
      (node (ref "D1") (pin "2") (pinfunction "K_2") (pintype "unspecified"))
      (node (ref "U3") (pin "1") (pinfunction "VIN_1") (pintype "unspecified"))
    )
    (net (code "37") (name "Net-(D2-C)") (class "Default")
      (node (ref "D2") (pin "1") (pinfunction "C_1") (pintype "unspecified"))
      (node (ref "R6") (pin "1") (pinfunction "1_1") (pintype "unspecified"))
      (node (ref "U4") (pin "4") (pinfunction "IO0_0_4") (pintype "unspecified"))
    )
    (net (code "38") (name "Net-(D3-C)") (class "Default")
      (node (ref "D3") (pin "1") (pinfunction "C_1") (pintype "unspecified"))
      (node (ref "R7") (pin "1") (pinfunction "1_1") (pintype "unspecified"))
      (node (ref "U4") (pin "5") (pinfunction "IO0_1_5") (pintype "unspecified"))
    )
    (net (code "39") (name "Net-(D4-C)") (class "Default")
      (node (ref "D4") (pin "1") (pinfunction "C_1") (pintype "unspecified"))
      (node (ref "R8") (pin "1") (pinfunction "1_1") (pintype "unspecified"))
      (node (ref "U4") (pin "6") (pinfunction "IO0_2_6") (pintype "unspecified"))
    )
    (net (code "40") (name "Net-(D5-C)") (class "Default")
      (node (ref "D5") (pin "1") (pinfunction "C_1") (pintype "unspecified"))
      (node (ref "R9") (pin "1") (pinfunction "1_1") (pintype "unspecified"))
      (node (ref "U4") (pin "7") (pinfunction "IO0_3_7") (pintype "unspecified"))
    )
    (net (code "41") (name "Net-(D6-C)") (class "Default")
      (node (ref "D6") (pin "1") (pinfunction "C_1") (pintype "unspecified"))
      (node (ref "R10") (pin "1") (pinfunction "1_1") (pintype "unspecified"))
      (node (ref "U4") (pin "8") (pinfunction "IO0_4_8") (pintype "unspecified"))
    )
    (net (code "42") (name "Net-(D7-C)") (class "Default")
      (node (ref "D7") (pin "1") (pinfunction "C_1") (pintype "unspecified"))
      (node (ref "R11") (pin "1") (pinfunction "1_1") (pintype "unspecified"))
      (node (ref "U4") (pin "9") (pinfunction "IO0_5_9") (pintype "unspecified"))
    )
    (net (code "43") (name "Net-(D8-C)") (class "Default")
      (node (ref "D8") (pin "1") (pinfunction "C_1") (pintype "unspecified"))
      (node (ref "R12") (pin "1") (pinfunction "1_1") (pintype "unspecified"))
      (node (ref "U4") (pin "10") (pinfunction "IO0_6_10") (pintype "unspecified"))
    )
    (net (code "44") (name "Net-(D9-C)") (class "Default")
      (node (ref "D9") (pin "1") (pinfunction "C_1") (pintype "unspecified"))
      (node (ref "R13") (pin "1") (pinfunction "1_1") (pintype "unspecified"))
      (node (ref "U4") (pin "11") (pinfunction "IO0_7_11") (pintype "unspecified"))
    )
    (net (code "45") (name "Net-(D10-A)") (class "Default")
      (node (ref "D10") (pin "2") (pinfunction "A_2") (pintype "unspecified"))
      (node (ref "U6") (pin "6") (pinfunction "LED0_6") (pintype "unspecified"))
    )
    (net (code "46") (name "Net-(D11-A)") (class "Default")
      (node (ref "D11") (pin "2") (pinfunction "A_2") (pintype "unspecified"))
      (node (ref "U6") (pin "23") (pinfunction "LED15_23") (pintype "unspecified"))
    )
    (net (code "47") (name "Net-(D12-A)") (class "Default")
      (node (ref "D12") (pin "2") (pinfunction "A_2") (pintype "unspecified"))
      (node (ref "U6") (pin "7") (pinfunction "LED1_7") (pintype "unspecified"))
    )
    (net (code "48") (name "Net-(D13-A)") (class "Default")
      (node (ref "D13") (pin "2") (pinfunction "A_2") (pintype "unspecified"))
      (node (ref "U6") (pin "22") (pinfunction "LED14_22") (pintype "unspecified"))
    )
    (net (code "49") (name "Net-(D14-A)") (class "Default")
      (node (ref "D14") (pin "2") (pinfunction "A_2") (pintype "unspecified"))
      (node (ref "U6") (pin "8") (pinfunction "LED2_8") (pintype "unspecified"))
    )
    (net (code "50") (name "Net-(D15-A)") (class "Default")
      (node (ref "D15") (pin "2") (pinfunction "A_2") (pintype "unspecified"))
      (node (ref "U6") (pin "21") (pinfunction "LED13_21") (pintype "unspecified"))
    )
    (net (code "51") (name "Net-(D16-A)") (class "Default")
      (node (ref "D16") (pin "2") (pinfunction "A_2") (pintype "unspecified"))
      (node (ref "U6") (pin "9") (pinfunction "LED3_9") (pintype "unspecified"))
    )
    (net (code "52") (name "Net-(D17-A)") (class "Default")
      (node (ref "D17") (pin "2") (pinfunction "A_2") (pintype "unspecified"))
      (node (ref "U6") (pin "20") (pinfunction "LED12_20") (pintype "unspecified"))
    )
    (net (code "53") (name "Net-(D18-A)") (class "Default")
      (node (ref "D18") (pin "2") (pinfunction "A_2") (pintype "unspecified"))
      (node (ref "U6") (pin "11") (pinfunction "LED4_11") (pintype "unspecified"))
    )
    (net (code "54") (name "Net-(D19-A)") (class "Default")
      (node (ref "D19") (pin "2") (pinfunction "A_2") (pintype "unspecified"))
      (node (ref "U6") (pin "18") (pinfunction "LED11_18") (pintype "unspecified"))
    )
    (net (code "55") (name "Net-(D20-A)") (class "Default")
      (node (ref "D20") (pin "2") (pinfunction "A_2") (pintype "unspecified"))
      (node (ref "U6") (pin "12") (pinfunction "LED5_12") (pintype "unspecified"))
    )
    (net (code "56") (name "Net-(D21-A)") (class "Default")
      (node (ref "D21") (pin "2") (pinfunction "A_2") (pintype "unspecified"))
      (node (ref "U6") (pin "17") (pinfunction "LED10_17") (pintype "unspecified"))
    )
    (net (code "57") (name "Net-(D22-A)") (class "Default")
      (node (ref "D22") (pin "2") (pinfunction "A_2") (pintype "unspecified"))
      (node (ref "U6") (pin "13") (pinfunction "LED6_13") (pintype "unspecified"))
    )
    (net (code "58") (name "Net-(D23-A)") (class "Default")
      (node (ref "D23") (pin "2") (pinfunction "A_2") (pintype "unspecified"))
      (node (ref "U6") (pin "16") (pinfunction "LED9_16") (pintype "unspecified"))
    )
    (net (code "59") (name "Net-(D24-A)") (class "Default")
      (node (ref "D24") (pin "2") (pinfunction "A_2") (pintype "unspecified"))
      (node (ref "U6") (pin "14") (pinfunction "LED7_14") (pintype "unspecified"))
    )
    (net (code "60") (name "Net-(D25-A)") (class "Default")
      (node (ref "D25") (pin "2") (pinfunction "A_2") (pintype "unspecified"))
      (node (ref "U6") (pin "15") (pinfunction "LED8_15") (pintype "unspecified"))
    )
    (net (code "61") (name "Net-(U3-VOUT)") (class "Default")
      (node (ref "C4") (pin "1") (pinfunction "1_1") (pintype "unspecified"))
      (node (ref "J1") (pin "1") (pinfunction "1_1") (pintype "input"))
      (node (ref "U3") (pin "3") (pinfunction "VOUT_3") (pintype "unspecified"))
    )
    (net (code "62") (name "Net-(U5-LED0)") (class "Default")
      (node (ref "R16") (pin "1") (pinfunction "1_1") (pintype "unspecified"))
      (node (ref "U5") (pin "6") (pinfunction "LED0_6") (pintype "unspecified"))
    )
    (net (code "63") (name "Net-(U5-LED1)") (class "Default")
      (node (ref "R17") (pin "1") (pinfunction "1_1") (pintype "unspecified"))
      (node (ref "U5") (pin "7") (pinfunction "LED1_7") (pintype "unspecified"))
    )
    (net (code "64") (name "Net-(U5-LED2)") (class "Default")
      (node (ref "R18") (pin "1") (pinfunction "1_1") (pintype "unspecified"))
      (node (ref "U5") (pin "8") (pinfunction "LED2_8") (pintype "unspecified"))
    )
    (net (code "65") (name "Net-(U5-LED3)") (class "Default")
      (node (ref "R19") (pin "1") (pinfunction "1_1") (pintype "unspecified"))
      (node (ref "U5") (pin "9") (pinfunction "LED3_9") (pintype "unspecified"))
    )
    (net (code "66") (name "Net-(U5-LED4)") (class "Default")
      (node (ref "R20") (pin "1") (pinfunction "1_1") (pintype "unspecified"))
      (node (ref "U5") (pin "10") (pinfunction "LED4_10") (pintype "unspecified"))
    )
    (net (code "67") (name "Net-(U5-LED5)") (class "Default")
      (node (ref "R21") (pin "1") (pinfunction "1_1") (pintype "unspecified"))
      (node (ref "U5") (pin "11") (pinfunction "LED5_11") (pintype "unspecified"))
    )
    (net (code "68") (name "Net-(U5-LED6)") (class "Default")
      (node (ref "R22") (pin "1") (pinfunction "1_1") (pintype "unspecified"))
      (node (ref "U5") (pin "12") (pinfunction "LED6_12") (pintype "unspecified"))
    )
    (net (code "69") (name "Net-(U5-LED7)") (class "Default")
      (node (ref "R23") (pin "1") (pinfunction "1_1") (pintype "unspecified"))
      (node (ref "U5") (pin "13") (pinfunction "LED7_13") (pintype "unspecified"))
    )
    (net (code "70") (name "Net-(U6-REXT)") (class "Default")
      (node (ref "R15") (pin "1") (pinfunction "1_1") (pintype "unspecified"))
      (node (ref "U6") (pin "1") (pinfunction "REXT_1") (pintype "unspecified"))
    )
    (net (code "71") (name "RST") (class "Default")
      (node (ref "PCB1") (pin "38") (pinfunction "RST_38") (pintype "unspecified"))
      (node (ref "R14") (pin "2") (pinfunction "2_2") (pintype "unspecified"))
      (node (ref "U6") (pin "25") (pinfunction "RESET#_25") (pintype "unspecified"))
    )
    (net (code "72") (name "SCL") (class "Default")
      (node (ref "PCB1") (pin "36") (pinfunction "SCL_36") (pintype "unspecified"))
      (node (ref "U2") (pin "6") (pinfunction "SCL_6") (pintype "unspecified"))
      (node (ref "U4") (pin "22") (pinfunction "SCL_22") (pintype "unspecified"))
      (node (ref "U5") (pin "27") (pinfunction "SDA_27") (pintype "unspecified"))
      (node (ref "U6") (pin "26") (pinfunction "SCL_26") (pintype "unspecified"))
    )
    (net (code "73") (name "SDA") (class "Default")
      (node (ref "PCB1") (pin "37") (pinfunction "SDA_37") (pintype "unspecified"))
      (node (ref "U2") (pin "5") (pinfunction "SDA_5") (pintype "unspecified"))
      (node (ref "U4") (pin "23") (pinfunction "SDA_23") (pintype "unspecified"))
      (node (ref "U5") (pin "26") (pinfunction "SCL_26") (pintype "unspecified"))
      (node (ref "U6") (pin "27") (pinfunction "SDA_27") (pintype "unspecified"))
    )
    (net (code "74") (name "SEC-11") (class "Default")
      (node (ref "B1") (pin "AC1") (pinfunction "AC1_AC1") (pintype "unspecified"))
      (node (ref "H2") (pin "3") (pinfunction "3_3") (pintype "input"))
      (node (ref "R24") (pin "1") (pinfunction "1_1") (pintype "unspecified"))
      (node (ref "R26") (pin "1") (pinfunction "1_1") (pintype "unspecified"))
    )
    (net (code "75") (name "SEC-12") (class "Default")
      (node (ref "B3") (pin "AC1") (pinfunction "AC1_AC1") (pintype "unspecified"))
      (node (ref "H2") (pin "5") (pinfunction "5_5") (pintype "input"))
      (node (ref "R28") (pin "1") (pinfunction "1_1") (pintype "unspecified"))
      (node (ref "R30") (pin "1") (pinfunction "1_1") (pintype "unspecified"))
    )
    (net (code "76") (name "SEC-13") (class "Default")
      (node (ref "B5") (pin "AC1") (pinfunction "AC1_AC1") (pintype "unspecified"))
      (node (ref "H2") (pin "7") (pinfunction "7_7") (pintype "input"))
      (node (ref "R32") (pin "1") (pinfunction "1_1") (pintype "unspecified"))
      (node (ref "R34") (pin "1") (pinfunction "1_1") (pintype "unspecified"))
    )
    (net (code "77") (name "SEC-14") (class "Default")
      (node (ref "B7") (pin "AC1") (pinfunction "AC1_AC1") (pintype "unspecified"))
      (node (ref "H2") (pin "9") (pinfunction "9_9") (pintype "input"))
      (node (ref "R36") (pin "1") (pinfunction "1_1") (pintype "unspecified"))
      (node (ref "R38") (pin "1") (pinfunction "1_1") (pintype "unspecified"))
    )
    (net (code "78") (name "SEC-21") (class "Default")
      (node (ref "B2") (pin "AC2") (pinfunction "AC2_AC2") (pintype "unspecified"))
      (node (ref "H2") (pin "11") (pinfunction "11_11") (pintype "input"))
      (node (ref "R25") (pin "1") (pinfunction "1_1") (pintype "unspecified"))
      (node (ref "R27") (pin "1") (pinfunction "1_1") (pintype "unspecified"))
    )
    (net (code "79") (name "SEC-22") (class "Default")
      (node (ref "B4") (pin "AC2") (pinfunction "AC2_AC2") (pintype "unspecified"))
      (node (ref "H2") (pin "13") (pinfunction "13_13") (pintype "input"))
      (node (ref "R29") (pin "1") (pinfunction "1_1") (pintype "unspecified"))
      (node (ref "R31") (pin "1") (pinfunction "1_1") (pintype "unspecified"))
    )
    (net (code "80") (name "SEC-23") (class "Default")
      (node (ref "B6") (pin "AC2") (pinfunction "AC2_AC2") (pintype "unspecified"))
      (node (ref "H2") (pin "15") (pinfunction "15_15") (pintype "input"))
      (node (ref "R33") (pin "1") (pinfunction "1_1") (pintype "unspecified"))
      (node (ref "R35") (pin "1") (pinfunction "1_1") (pintype "unspecified"))
    )
    (net (code "81") (name "SEC-24") (class "Default")
      (node (ref "B8") (pin "AC2") (pinfunction "AC2_AC2") (pintype "unspecified"))
      (node (ref "H2") (pin "17") (pinfunction "17_17") (pintype "input"))
      (node (ref "R37") (pin "1") (pinfunction "1_1") (pintype "unspecified"))
      (node (ref "R39") (pin "1") (pinfunction "1_1") (pintype "unspecified"))
    )
    (net (code "82") (name "SIG-0") (class "Default")
      (node (ref "D11") (pin "1") (pinfunction "C_1") (pintype "unspecified"))
      (node (ref "H1") (pin "13") (pinfunction "13_13") (pintype "input"))
    )
    (net (code "83") (name "SIG-1") (class "Default")
      (node (ref "D13") (pin "1") (pinfunction "C_1") (pintype "unspecified"))
      (node (ref "H1") (pin "14") (pinfunction "14_14") (pintype "input"))
    )
    (net (code "84") (name "SIG-2") (class "Default")
      (node (ref "D15") (pin "1") (pinfunction "C_1") (pintype "unspecified"))
      (node (ref "H1") (pin "15") (pinfunction "15_15") (pintype "input"))
    )
    (net (code "85") (name "SIG-3") (class "Default")
      (node (ref "D17") (pin "1") (pinfunction "C_1") (pintype "unspecified"))
      (node (ref "H1") (pin "16") (pinfunction "16_16") (pintype "input"))
    )
    (net (code "86") (name "SIG-4") (class "Default")
      (node (ref "D19") (pin "1") (pinfunction "C_1") (pintype "unspecified"))
      (node (ref "H1") (pin "17") (pinfunction "17_17") (pintype "input"))
    )
    (net (code "87") (name "SIG-5") (class "Default")
      (node (ref "D21") (pin "1") (pinfunction "C_1") (pintype "unspecified"))
      (node (ref "H1") (pin "18") (pinfunction "18_18") (pintype "input"))
    )
    (net (code "88") (name "SIG-6") (class "Default")
      (node (ref "D23") (pin "1") (pinfunction "C_1") (pintype "unspecified"))
      (node (ref "H1") (pin "19") (pinfunction "19_19") (pintype "input"))
    )
    (net (code "89") (name "SIG-7") (class "Default")
      (node (ref "D25") (pin "1") (pinfunction "C_1") (pintype "unspecified"))
      (node (ref "H1") (pin "20") (pinfunction "20_20") (pintype "input"))
    )
    (net (code "90") (name "SIG-8") (class "Default")
      (node (ref "D24") (pin "1") (pinfunction "C_1") (pintype "unspecified"))
      (node (ref "H1") (pin "21") (pinfunction "21_21") (pintype "input"))
    )
    (net (code "91") (name "SIG-9") (class "Default")
      (node (ref "D22") (pin "1") (pinfunction "C_1") (pintype "unspecified"))
      (node (ref "H1") (pin "22") (pinfunction "22_22") (pintype "input"))
    )
    (net (code "92") (name "SIG-10") (class "Default")
      (node (ref "D20") (pin "1") (pinfunction "C_1") (pintype "unspecified"))
      (node (ref "H1") (pin "23") (pinfunction "23_23") (pintype "input"))
    )
    (net (code "93") (name "SIG-11") (class "Default")
      (node (ref "D18") (pin "1") (pinfunction "C_1") (pintype "unspecified"))
      (node (ref "H1") (pin "24") (pinfunction "24_24") (pintype "input"))
    )
    (net (code "94") (name "SIG-12") (class "Default")
      (node (ref "D16") (pin "1") (pinfunction "C_1") (pintype "unspecified"))
      (node (ref "H1") (pin "25") (pinfunction "25_25") (pintype "input"))
    )
    (net (code "95") (name "SIG-13") (class "Default")
      (node (ref "D14") (pin "1") (pinfunction "C_1") (pintype "unspecified"))
      (node (ref "H1") (pin "26") (pinfunction "26_26") (pintype "input"))
    )
    (net (code "96") (name "SIG-14") (class "Default")
      (node (ref "D12") (pin "1") (pinfunction "C_1") (pintype "unspecified"))
      (node (ref "H1") (pin "27") (pinfunction "27_27") (pintype "input"))
    )
    (net (code "97") (name "SIG-15") (class "Default")
      (node (ref "D10") (pin "1") (pinfunction "C_1") (pintype "unspecified"))
      (node (ref "H1") (pin "28") (pinfunction "28_28") (pintype "input"))
    )
    (net (code "98") (name "SRV-0") (class "Default")
      (node (ref "H1") (pin "31") (pinfunction "31_31") (pintype "input"))
      (node (ref "R23") (pin "2") (pinfunction "2_2") (pintype "unspecified"))
    )
    (net (code "99") (name "SRV-1") (class "Default")
      (node (ref "H1") (pin "32") (pinfunction "32_32") (pintype "input"))
      (node (ref "R22") (pin "2") (pinfunction "2_2") (pintype "unspecified"))
    )
    (net (code "100") (name "SRV-2") (class "Default")
      (node (ref "H1") (pin "33") (pinfunction "33_33") (pintype "input"))
      (node (ref "R21") (pin "2") (pinfunction "2_2") (pintype "unspecified"))
    )
    (net (code "101") (name "SRV-3") (class "Default")
      (node (ref "H1") (pin "34") (pinfunction "34_34") (pintype "input"))
      (node (ref "R20") (pin "2") (pinfunction "2_2") (pintype "unspecified"))
    )
    (net (code "102") (name "SRV-4") (class "Default")
      (node (ref "H1") (pin "35") (pinfunction "35_35") (pintype "input"))
      (node (ref "R19") (pin "2") (pinfunction "2_2") (pintype "unspecified"))
    )
    (net (code "103") (name "SRV-5") (class "Default")
      (node (ref "H1") (pin "36") (pinfunction "36_36") (pintype "input"))
      (node (ref "R18") (pin "2") (pinfunction "2_2") (pintype "unspecified"))
    )
    (net (code "104") (name "SRV-6") (class "Default")
      (node (ref "H1") (pin "37") (pinfunction "37_37") (pintype "input"))
      (node (ref "R17") (pin "2") (pinfunction "2_2") (pintype "unspecified"))
    )
    (net (code "105") (name "SRV-7") (class "Default")
      (node (ref "H1") (pin "38") (pinfunction "38_38") (pintype "input"))
      (node (ref "R16") (pin "2") (pinfunction "2_2") (pintype "unspecified"))
    )
    (net (code "106") (name "TRACK-1-1") (class "Default")
      (node (ref "PCB1") (pin "1") (pinfunction "I-PB-1_1") (pintype "unspecified"))
    )
    (net (code "107") (name "TRACK-1-2") (class "Default")
      (node (ref "PCB1") (pin "2") (pinfunction "I-PB-2_2") (pintype "unspecified"))
    )
    (net (code "108") (name "TRACK-2-1") (class "Default")
      (node (ref "PCB1") (pin "3") (pinfunction "I-PB-3_3") (pintype "unspecified"))
    )
    (net (code "109") (name "TRACK-2-2") (class "Default")
      (node (ref "PCB1") (pin "4") (pinfunction "I-PB-4_4") (pintype "unspecified"))
    )
    (net (code "110") (name "TRACK-3-1") (class "Default")
      (node (ref "PCB1") (pin "5") (pinfunction "I-PB-5_5") (pintype "unspecified"))
    )
    (net (code "111") (name "TRACK-3-2") (class "Default")
      (node (ref "PCB1") (pin "6") (pinfunction "I-PB-6_6") (pintype "unspecified"))
    )
    (net (code "112") (name "TRACK-4-1") (class "Default")
      (node (ref "PCB1") (pin "7") (pinfunction "I-PB-7_7") (pintype "unspecified"))
    )
    (net (code "113") (name "TRACK-4-2") (class "Default")
      (node (ref "PCB1") (pin "8") (pinfunction "I-PB-8_8") (pintype "unspecified"))
    )
    (net (code "114") (name "TRACK-A-1") (class "Default")
      (node (ref "B1") (pin "AC2") (pinfunction "AC2_AC2") (pintype "unspecified"))
      (node (ref "B3") (pin "AC2") (pinfunction "AC2_AC2") (pintype "unspecified"))
      (node (ref "B5") (pin "AC2") (pinfunction "AC2_AC2") (pintype "unspecified"))
      (node (ref "B7") (pin "AC2") (pinfunction "AC2_AC2") (pintype "unspecified"))
      (node (ref "R24") (pin "2") (pinfunction "2_2") (pintype "unspecified"))
      (node (ref "R28") (pin "2") (pinfunction "2_2") (pintype "unspecified"))
      (node (ref "R32") (pin "2") (pinfunction "2_2") (pintype "unspecified"))
      (node (ref "R36") (pin "2") (pinfunction "2_2") (pintype "unspecified"))
      (node (ref "U7") (pin "1") (pinfunction "1_1") (pintype "unspecified"))
      (node (ref "U7") (pin "3") (pinfunction "3_3") (pintype "unspecified"))
      (node (ref "U7") (pin "5") (pinfunction "5_5") (pintype "unspecified"))
      (node (ref "U7") (pin "7") (pinfunction "7_7") (pintype "unspecified"))
    )
    (net (code "115") (name "TRACK-B-1") (class "Default")
      (node (ref "B2") (pin "AC1") (pinfunction "AC1_AC1") (pintype "unspecified"))
      (node (ref "B4") (pin "AC1") (pinfunction "AC1_AC1") (pintype "unspecified"))
      (node (ref "B6") (pin "AC1") (pinfunction "AC1_AC1") (pintype "unspecified"))
      (node (ref "B8") (pin "AC1") (pinfunction "AC1_AC1") (pintype "unspecified"))
      (node (ref "R25") (pin "2") (pinfunction "2_2") (pintype "unspecified"))
      (node (ref "R29") (pin "2") (pinfunction "2_2") (pintype "unspecified"))
      (node (ref "R33") (pin "2") (pinfunction "2_2") (pintype "unspecified"))
      (node (ref "R37") (pin "2") (pinfunction "2_2") (pintype "unspecified"))
      (node (ref "U8") (pin "1") (pinfunction "1_1") (pintype "unspecified"))
      (node (ref "U8") (pin "3") (pinfunction "3_3") (pintype "unspecified"))
      (node (ref "U8") (pin "5") (pinfunction "5_5") (pintype "unspecified"))
      (node (ref "U8") (pin "7") (pinfunction "7_7") (pintype "unspecified"))
    )
    (net (code "116") (name "Track-1-1") (class "Default")
      (node (ref "J2") (pin "1") (pinfunction "1_1") (pintype "input"))
    )
    (net (code "117") (name "Track-1-2") (class "Default")
      (node (ref "J3") (pin "1") (pinfunction "1_1") (pintype "input"))
    )
    (net (code "118") (name "Track-2-1") (class "Default")
      (node (ref "J2") (pin "3") (pinfunction "3_3") (pintype "input"))
    )
    (net (code "119") (name "Track-2-2") (class "Default")
      (node (ref "J3") (pin "3") (pinfunction "3_3") (pintype "input"))
    )
    (net (code "120") (name "Track-3-1") (class "Default")
      (node (ref "J4") (pin "1") (pinfunction "1_1") (pintype "input"))
    )
    (net (code "121") (name "Track-3-2") (class "Default")
      (node (ref "J5") (pin "1") (pinfunction "1_1") (pintype "input"))
    )
    (net (code "122") (name "Track-4-1") (class "Default")
      (node (ref "J4") (pin "3") (pinfunction "3_3") (pintype "input"))
    )
    (net (code "123") (name "Track-4-2") (class "Default")
      (node (ref "J5") (pin "3") (pinfunction "3_3") (pintype "input"))
    )
    (net (code "124") (name "Track-A-1") (class "Default")
      (node (ref "J2") (pin "2") (pinfunction "2_2") (pintype "input"))
    )
    (net (code "125") (name "Track-A-2") (class "Default")
      (node (ref "H2") (pin "1") (pinfunction "1_1") (pintype "input"))
      (node (ref "H2") (pin "10") (pinfunction "10_10") (pintype "input"))
      (node (ref "H2") (pin "2") (pinfunction "2_2") (pintype "input"))
      (node (ref "H2") (pin "4") (pinfunction "4_4") (pintype "input"))
      (node (ref "H2") (pin "6") (pinfunction "6_6") (pintype "input"))
      (node (ref "H2") (pin "8") (pinfunction "8_8") (pintype "input"))
      (node (ref "J3") (pin "2") (pinfunction "2_2") (pintype "input"))
    )
    (net (code "126") (name "Track-B-1") (class "Default")
      (node (ref "J4") (pin "2") (pinfunction "2_2") (pintype "input"))
    )
    (net (code "127") (name "Track-B-2") (class "Default")
      (node (ref "H2") (pin "12") (pinfunction "12_12") (pintype "input"))
      (node (ref "H2") (pin "14") (pinfunction "14_14") (pintype "input"))
      (node (ref "H2") (pin "16") (pinfunction "16_16") (pintype "input"))
      (node (ref "H2") (pin "18") (pinfunction "18_18") (pintype "input"))
      (node (ref "H2") (pin "19") (pinfunction "19_19") (pintype "input"))
      (node (ref "H2") (pin "20") (pinfunction "20_20") (pintype "input"))
      (node (ref "J5") (pin "2") (pinfunction "2_2") (pintype "input"))
    )
    (net (code "128") (name "VCC") (class "Default")
      (node (ref "C2") (pin "2") (pinfunction "2_2") (pintype "unspecified"))
      (node (ref "C5") (pin "1") (pinfunction "1_1") (pintype "unspecified"))
      (node (ref "J1") (pin "3") (pinfunction "3_3") (pintype "input"))
      (node (ref "PCB1") (pin "40") (pinfunction "VCC_40") (pintype "unspecified"))
      (node (ref "PCB1") (pin "41") (pinfunction "VCC_41") (pintype "unspecified"))
      (node (ref "R40") (pin "2") (pinfunction "2_2") (pintype "unspecified"))
      (node (ref "R41") (pin "2") (pinfunction "2_2") (pintype "unspecified"))
      (node (ref "R42") (pin "2") (pinfunction "2_2") (pintype "unspecified"))
      (node (ref "R43") (pin "2") (pinfunction "2_2") (pintype "unspecified"))
      (node (ref "R44") (pin "2") (pinfunction "2_2") (pintype "unspecified"))
      (node (ref "R45") (pin "2") (pinfunction "2_2") (pintype "unspecified"))
      (node (ref "R46") (pin "2") (pinfunction "2_2") (pintype "unspecified"))
      (node (ref "R47") (pin "2") (pinfunction "2_2") (pintype "unspecified"))
      (node (ref "U2") (pin "8") (pinfunction "VCC_8") (pintype "unspecified"))
      (node (ref "U4") (pin "24") (pinfunction "VDD_24") (pintype "unspecified"))
    )
    (net (code "129") (name "VS") (class "Default")
      (node (ref "D1") (pin "1") (pinfunction "A_1") (pintype "unspecified"))
      (node (ref "PCB1") (pin "44") (pinfunction "VS_44") (pintype "unspecified"))
      (node (ref "PCB1") (pin "45") (pinfunction "VS_45") (pintype "unspecified"))
      (node (ref "PCB1") (pin "46") (pinfunction "VS_46") (pintype "unspecified"))
      (node (ref "PCB1") (pin "47") (pinfunction "VS_47") (pintype "unspecified"))
    )
    (net (code "130") (name "VSB") (class "Default")
      (node (ref "C6") (pin "1") (pinfunction "1_1") (pintype "unspecified"))
      (node (ref "C7") (pin "2") (pinfunction "2_2") (pintype "unspecified"))
      (node (ref "C9") (pin "1") (pinfunction "1_1") (pintype "unspecified"))
      (node (ref "H1") (pin "39") (pinfunction "39_39") (pintype "input"))
      (node (ref "H1") (pin "40") (pinfunction "40_40") (pintype "input"))
      (node (ref "J1") (pin "2") (pinfunction "2_2") (pintype "input"))
      (node (ref "R14") (pin "1") (pinfunction "1_1") (pintype "unspecified"))
      (node (ref "U5") (pin "24") (pinfunction "A5_24") (pintype "unspecified"))
      (node (ref "U5") (pin "28") (pinfunction "VDD_28") (pintype "unspecified"))
      (node (ref "U5") (pin "4") (pinfunction "A3_4") (pintype "unspecified"))
      (node (ref "U5") (pin "5") (pinfunction "A4_5") (pintype "unspecified"))
      (node (ref "U6") (pin "28") (pinfunction "VDD_28") (pintype "unspecified"))
      (node (ref "U6") (pin "5") (pinfunction "A3_5") (pintype "unspecified"))
    )
    (net (code "131") (name "unconnected-(PCB1-ADC-0-Pad14)") (class "Default")
      (node (ref "PCB1") (pin "14") (pinfunction "ADC-0_14") (pintype "unspecified+no_connect"))
    )
    (net (code "132") (name "unconnected-(PCB1-ADC-1-Pad15)") (class "Default")
      (node (ref "PCB1") (pin "15") (pinfunction "ADC-1_15") (pintype "unspecified+no_connect"))
    )
    (net (code "133") (name "unconnected-(PCB1-BC-2-Pad34)") (class "Default")
      (node (ref "PCB1") (pin "34") (pinfunction "BC-2_34") (pintype "unspecified+no_connect"))
    )
    (net (code "134") (name "unconnected-(PCB1-BC-3-Pad35)") (class "Default")
      (node (ref "PCB1") (pin "35") (pinfunction "BC-3_35") (pintype "unspecified+no_connect"))
    )
    (net (code "135") (name "unconnected-(PCB1-DCC-1-Pad10)") (class "Default")
      (node (ref "PCB1") (pin "10") (pinfunction "DCC-1_10") (pintype "unspecified+no_connect"))
    )
    (net (code "136") (name "unconnected-(PCB1-DCC-2-Pad11)") (class "Default")
      (node (ref "PCB1") (pin "11") (pinfunction "DCC-2_11") (pintype "unspecified+no_connect"))
    )
    (net (code "137") (name "unconnected-(PCB1-DIO-0-Pad18)") (class "Default")
      (node (ref "PCB1") (pin "18") (pinfunction "DIO-0_18") (pintype "unspecified+no_connect"))
    )
    (net (code "138") (name "unconnected-(PCB1-DIO-1-Pad19)") (class "Default")
      (node (ref "PCB1") (pin "19") (pinfunction "DIO-1_19") (pintype "unspecified+no_connect"))
    )
    (net (code "139") (name "unconnected-(PCB1-DIO-2-Pad20)") (class "Default")
      (node (ref "PCB1") (pin "20") (pinfunction "DIO-2_20") (pintype "unspecified+no_connect"))
    )
    (net (code "140") (name "unconnected-(PCB1-DIO-3-Pad21)") (class "Default")
      (node (ref "PCB1") (pin "21") (pinfunction "DIO-3_21") (pintype "unspecified+no_connect"))
    )
    (net (code "141") (name "unconnected-(PCB1-DIO-4-Pad22)") (class "Default")
      (node (ref "PCB1") (pin "22") (pinfunction "DIO-4_22") (pintype "unspecified+no_connect"))
    )
    (net (code "142") (name "unconnected-(PCB1-DIO-5-Pad23)") (class "Default")
      (node (ref "PCB1") (pin "23") (pinfunction "DIO-5_23") (pintype "unspecified+no_connect"))
    )
    (net (code "143") (name "unconnected-(PCB1-DIO-6-Pad24)") (class "Default")
      (node (ref "PCB1") (pin "24") (pinfunction "DIO-6_24") (pintype "unspecified+no_connect"))
    )
    (net (code "144") (name "unconnected-(PCB1-DIO-7-Pad25)") (class "Default")
      (node (ref "PCB1") (pin "25") (pinfunction "DIO-7_25") (pintype "unspecified+no_connect"))
    )
    (net (code "145") (name "unconnected-(PCB1-DIO-8-Pad26)") (class "Default")
      (node (ref "PCB1") (pin "26") (pinfunction "DIO-8_26") (pintype "unspecified+no_connect"))
    )
    (net (code "146") (name "unconnected-(PCB1-DIO-9-Pad27)") (class "Default")
      (node (ref "PCB1") (pin "27") (pinfunction "DIO-9_27") (pintype "unspecified+no_connect"))
    )
    (net (code "147") (name "unconnected-(PCB1-DIO-10-Pad28)") (class "Default")
      (node (ref "PCB1") (pin "28") (pinfunction "DIO-10_28") (pintype "unspecified+no_connect"))
    )
    (net (code "148") (name "unconnected-(PCB1-DIO-11-Pad29)") (class "Default")
      (node (ref "PCB1") (pin "29") (pinfunction "DIO-11_29") (pintype "unspecified+no_connect"))
    )
    (net (code "149") (name "unconnected-(PCB1-EXT-Pad39)") (class "Default")
      (node (ref "PCB1") (pin "39") (pinfunction "EXT_39") (pintype "unspecified+no_connect"))
    )
    (net (code "150") (name "unconnected-(U4-INT#-Pad1)") (class "Default")
      (node (ref "U4") (pin "1") (pinfunction "INT#_1") (pintype "unspecified+no_connect"))
    )
    (net (code "151") (name "unconnected-(U5-EXTCLK-Pad25)") (class "Default")
      (node (ref "U5") (pin "25") (pinfunction "EXTCLK_25") (pintype "unspecified+no_connect"))
    )
    (net (code "152") (name "unconnected-(U5-LED8-Pad15)") (class "Default")
      (node (ref "U5") (pin "15") (pinfunction "LED8_15") (pintype "unspecified+no_connect"))
    )
    (net (code "153") (name "unconnected-(U5-LED9-Pad16)") (class "Default")
      (node (ref "U5") (pin "16") (pinfunction "LED9_16") (pintype "unspecified+no_connect"))
    )
    (net (code "154") (name "unconnected-(U5-LED10-Pad17)") (class "Default")
      (node (ref "U5") (pin "17") (pinfunction "LED10_17") (pintype "unspecified+no_connect"))
    )
    (net (code "155") (name "unconnected-(U5-LED11-Pad18)") (class "Default")
      (node (ref "U5") (pin "18") (pinfunction "LED11_18") (pintype "unspecified+no_connect"))
    )
    (net (code "156") (name "unconnected-(U5-LED12-Pad19)") (class "Default")
      (node (ref "U5") (pin "19") (pinfunction "LED12_19") (pintype "unspecified+no_connect"))
    )
    (net (code "157") (name "unconnected-(U5-LED13-Pad20)") (class "Default")
      (node (ref "U5") (pin "20") (pinfunction "LED13_20") (pintype "unspecified+no_connect"))
    )
    (net (code "158") (name "unconnected-(U5-LED14-Pad21)") (class "Default")
      (node (ref "U5") (pin "21") (pinfunction "LED14_21") (pintype "unspecified+no_connect"))
    )
    (net (code "159") (name "unconnected-(U5-LED15-Pad22)") (class "Default")
      (node (ref "U5") (pin "22") (pinfunction "LED15_22") (pintype "unspecified+no_connect"))
    )
    (net (code "160") (name "unconnected-(U5-OE#-Pad23)") (class "Default")
      (node (ref "U5") (pin "23") (pinfunction "OE#_23") (pintype "unspecified+no_connect"))
    )
  )
)
